# HashUnit4.net
KiCad netlist of a schematic drawn in Altium Designer
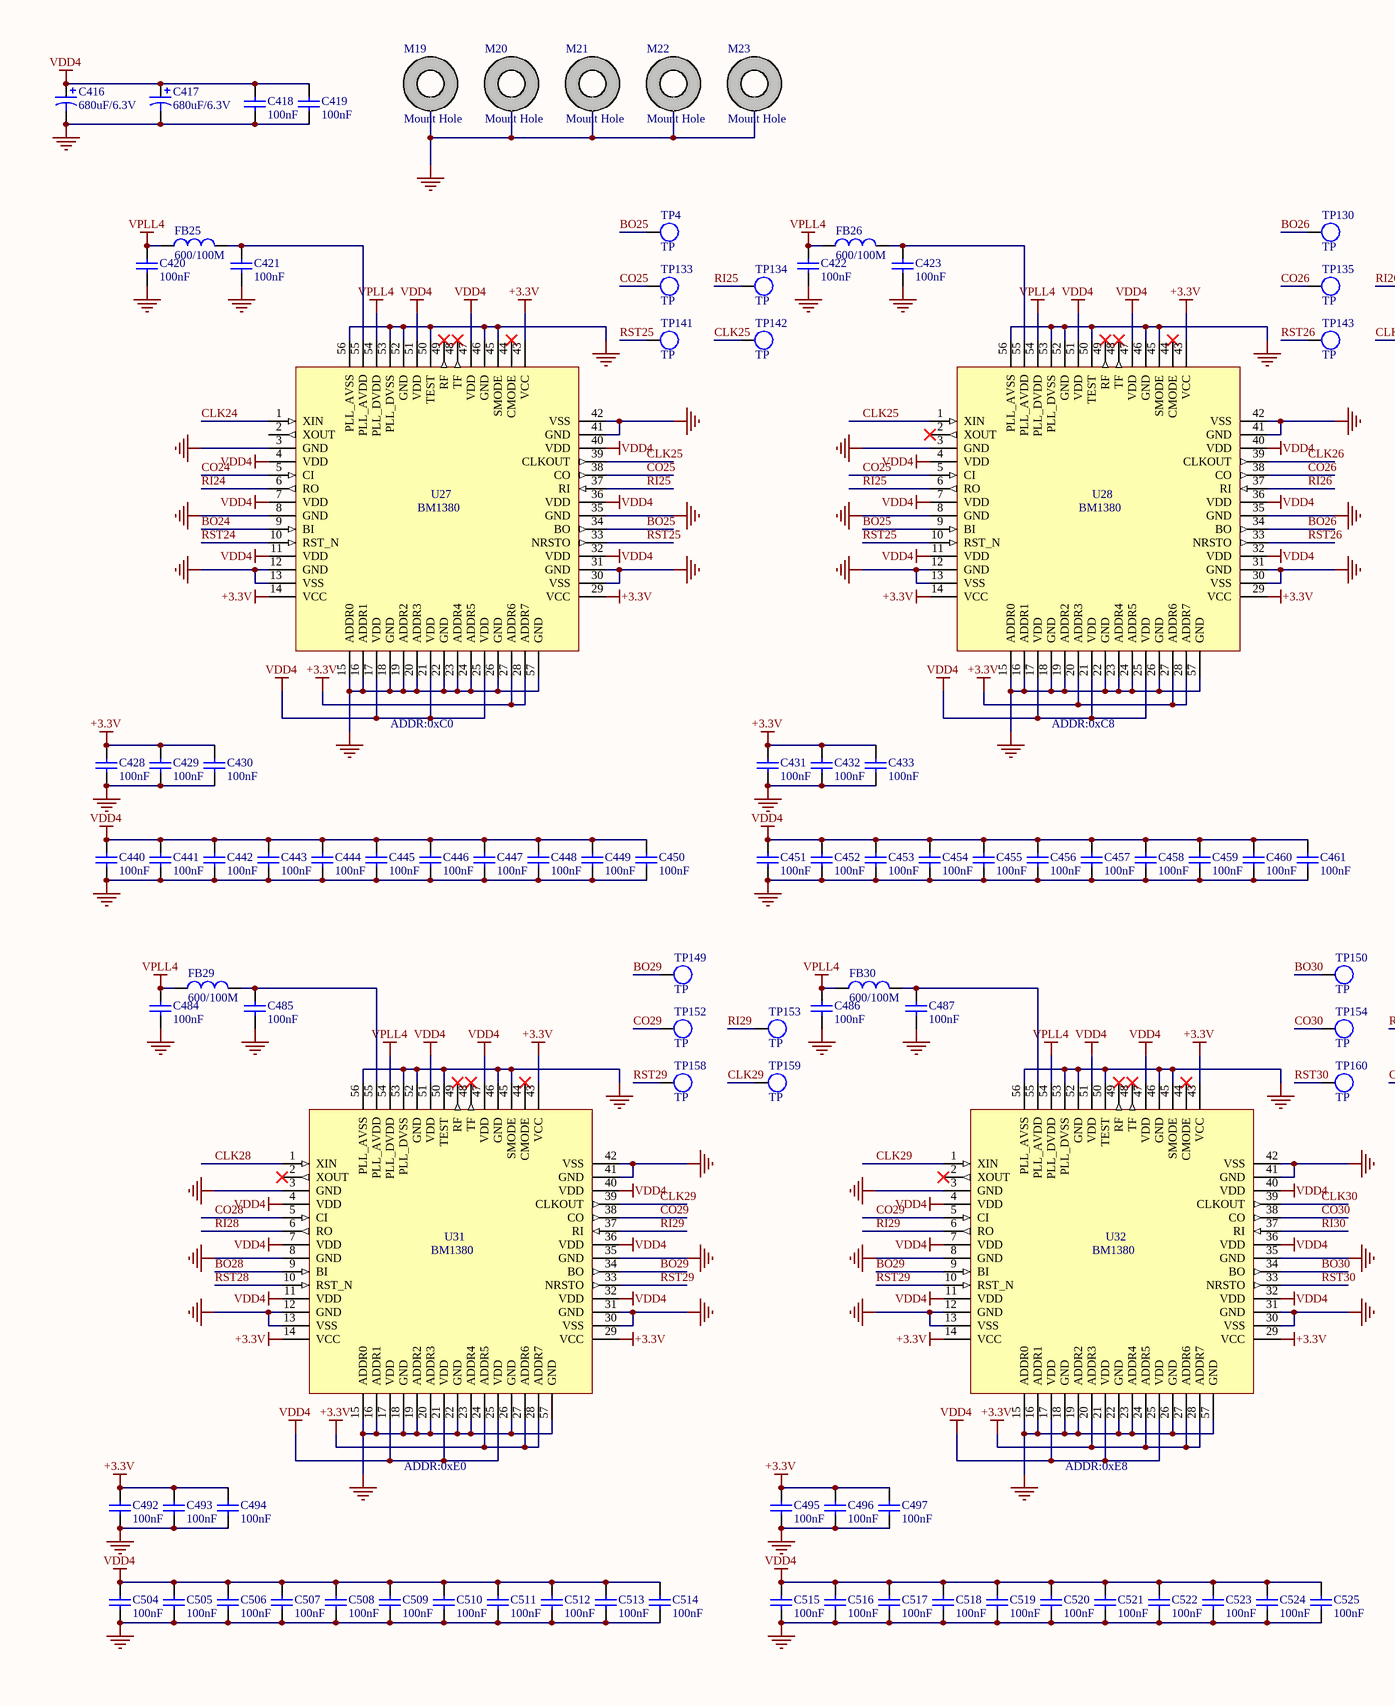
[diagram p0: HashUnit4.SchDoc, left]
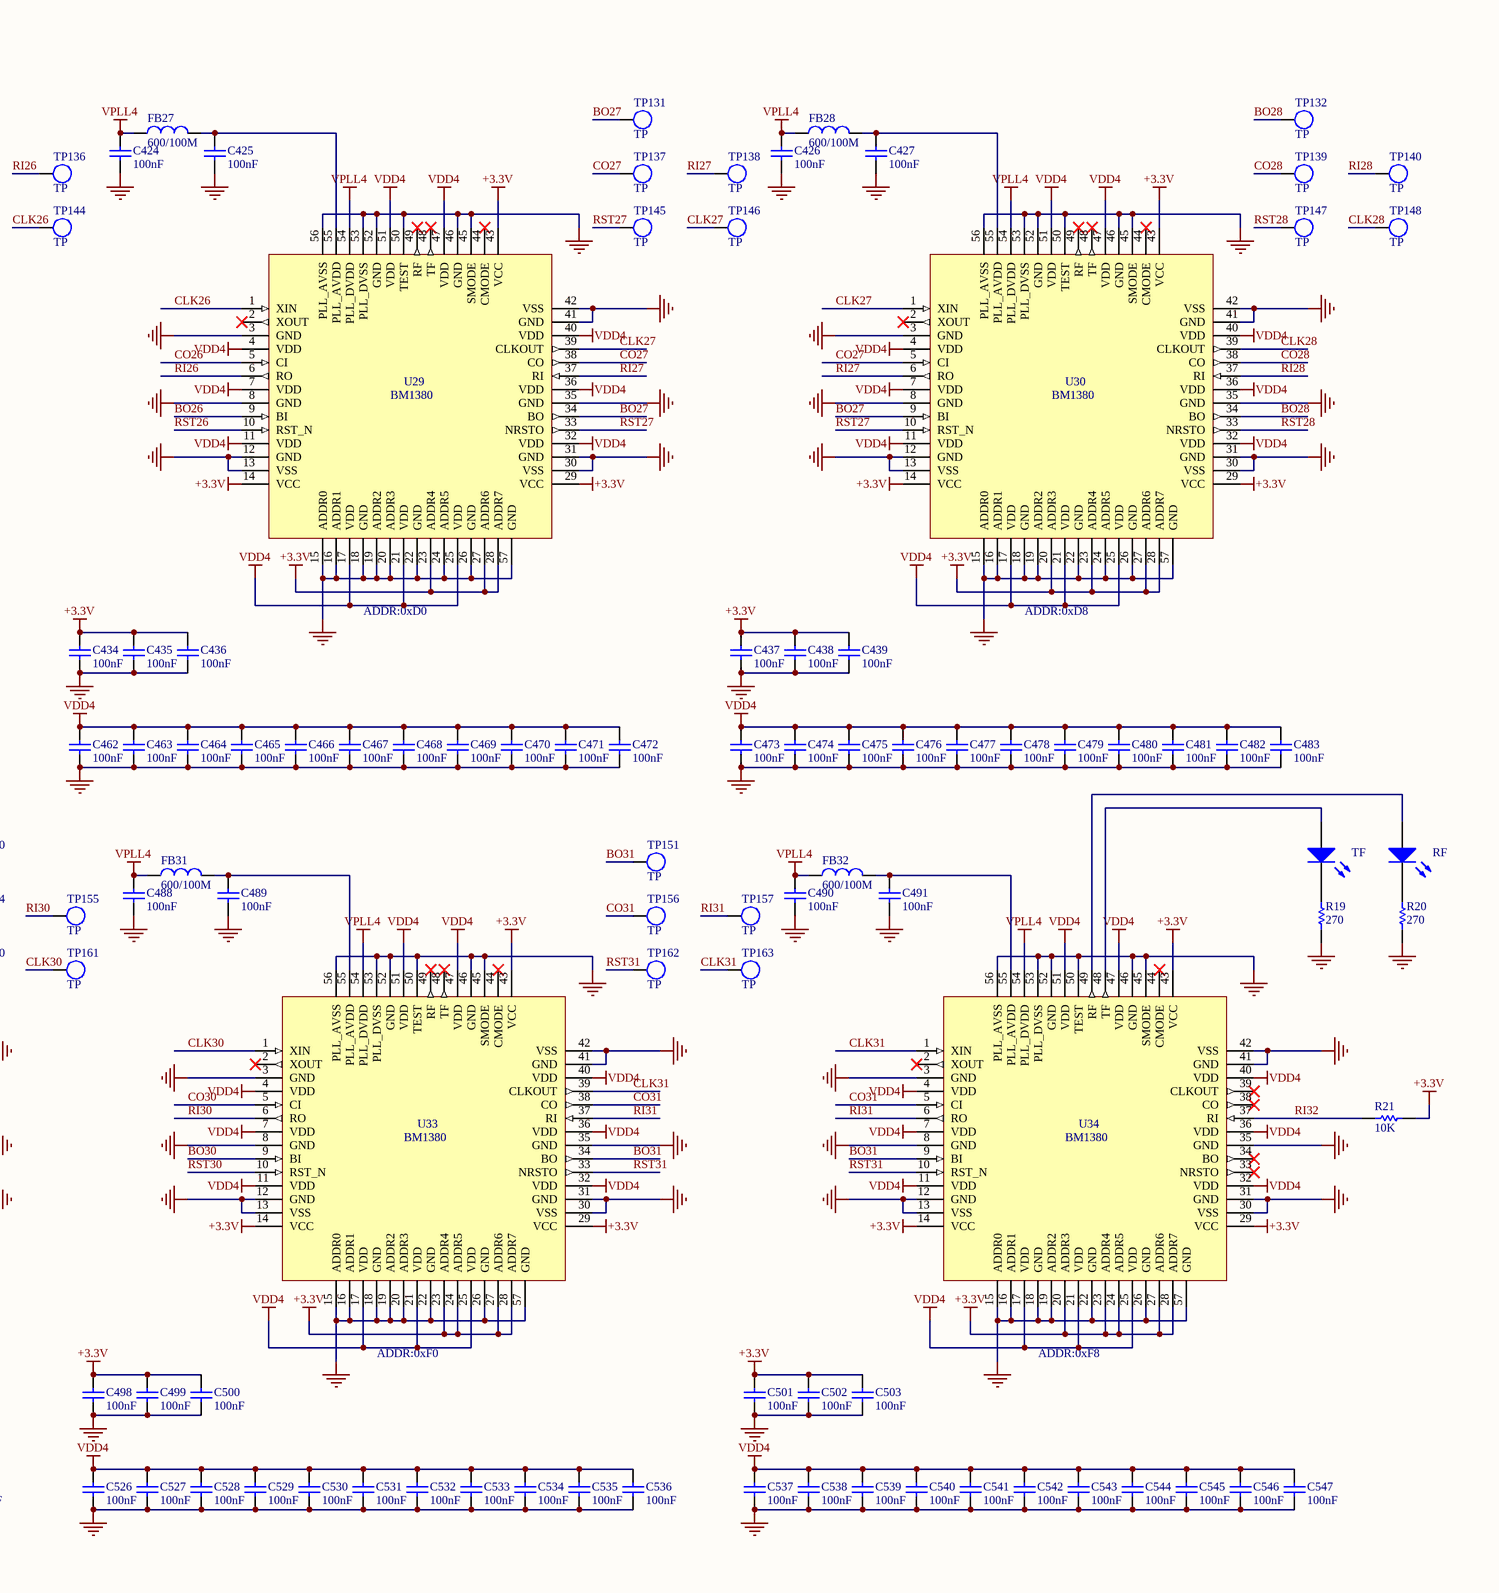
[diagram p1: HashUnit4.SchDoc, right]

(export (version "E")
  (design (tool "Eeschema 10.0.6"))
  (components
    (comp (ref "C416")
      (value "680uF/6.3V")
      (footprint "D")
      (description "Solid Tantalum Chip Capacitor, T492 Series - CWR11 Style Per Mil-PRF-55365/8")
      (fields (field (name "PUBLISHER") "Altium Limited"))
      (libsource (lib "KEMET Chip Capacitor") (part "T492C"))
    )
    (comp (ref "C417")
      (value "680uF/6.3V")
      (footprint "D")
      (description "Solid Tantalum Chip Capacitor, T492 Series - CWR11 Style Per Mil-PRF-55365/8")
      (fields (field (name "PUBLISHER") "Altium Limited"))
      (libsource (lib "KEMET Chip Capacitor") (part "T492C"))
    )
    (comp (ref "C418")
      (value "100nF")
      (footprint "CC0603(1608)")
      (description "Capacitor (Semiconductor SIM Model)")
      (fields (field (name "PUBLISHER") "Altium Limited"))
      (libsource (lib "Miscellaneous Devices") (part "Cap Semi"))
    )
    (comp (ref "C419")
      (value "100nF")
      (footprint "CC0603(1608)")
      (description "Capacitor (Semiconductor SIM Model)")
      (fields (field (name "PUBLISHER") "Altium Limited"))
      (libsource (lib "Miscellaneous Devices") (part "Cap Semi"))
    )
    (comp (ref "C420")
      (value "100nF")
      (footprint "CC0603(1608)")
      (description "Capacitor")
      (fields (field (name "PUBLISHER") "Altium Limited"))
      (libsource (lib "BitMain_Miner_1") (part "Cap"))
    )
    (comp (ref "C421")
      (value "100nF")
      (footprint "CC0603(1608)")
      (description "Capacitor")
      (fields (field (name "PUBLISHER") "Altium Limited"))
      (libsource (lib "BitMain_Miner_1") (part "Cap"))
    )
    (comp (ref "C422")
      (value "100nF")
      (footprint "CC0603(1608)")
      (description "Capacitor")
      (fields (field (name "PUBLISHER") "Altium Limited"))
      (libsource (lib "BitMain_Miner_1") (part "Cap"))
    )
    (comp (ref "C423")
      (value "100nF")
      (footprint "CC0603(1608)")
      (description "Capacitor")
      (fields (field (name "PUBLISHER") "Altium Limited"))
      (libsource (lib "BitMain_Miner_1") (part "Cap"))
    )
    (comp (ref "C424")
      (value "100nF")
      (footprint "CC0603(1608)")
      (description "Capacitor")
      (fields (field (name "PUBLISHER") "Altium Limited"))
      (libsource (lib "BitMain_Miner_1") (part "Cap"))
    )
    (comp (ref "C425")
      (value "100nF")
      (footprint "CC0603(1608)")
      (description "Capacitor")
      (fields (field (name "PUBLISHER") "Altium Limited"))
      (libsource (lib "BitMain_Miner_1") (part "Cap"))
    )
    (comp (ref "C426")
      (value "100nF")
      (footprint "CC0603(1608)")
      (description "Capacitor")
      (fields (field (name "PUBLISHER") "Altium Limited"))
      (libsource (lib "BitMain_Miner_1") (part "Cap"))
    )
    (comp (ref "C427")
      (value "100nF")
      (footprint "CC0603(1608)")
      (description "Capacitor")
      (fields (field (name "PUBLISHER") "Altium Limited"))
      (libsource (lib "BitMain_Miner_1") (part "Cap"))
    )
    (comp (ref "C428")
      (value "100nF")
      (footprint "CC0603(1608)")
      (description "Capacitor")
      (fields (field (name "PUBLISHER") "Altium Limited"))
      (libsource (lib "BitMain_Miner_1") (part "Cap"))
    )
    (comp (ref "C429")
      (value "100nF")
      (footprint "CC0603(1608)")
      (description "Capacitor")
      (fields (field (name "PUBLISHER") "Altium Limited"))
      (libsource (lib "BitMain_Miner_1") (part "Cap"))
    )
    (comp (ref "C430")
      (value "100nF")
      (footprint "CC0603(1608)")
      (description "Capacitor")
      (fields (field (name "PUBLISHER") "Altium Limited"))
      (libsource (lib "BitMain_Miner_1") (part "Cap"))
    )
    (comp (ref "C431")
      (value "100nF")
      (footprint "CC0603(1608)")
      (description "Capacitor")
      (fields (field (name "PUBLISHER") "Altium Limited"))
      (libsource (lib "BitMain_Miner_1") (part "Cap"))
    )
    (comp (ref "C432")
      (value "100nF")
      (footprint "CC0603(1608)")
      (description "Capacitor")
      (fields (field (name "PUBLISHER") "Altium Limited"))
      (libsource (lib "BitMain_Miner_1") (part "Cap"))
    )
    (comp (ref "C433")
      (value "100nF")
      (footprint "CC0603(1608)")
      (description "Capacitor")
      (fields (field (name "PUBLISHER") "Altium Limited"))
      (libsource (lib "BitMain_Miner_1") (part "Cap"))
    )
    (comp (ref "C434")
      (value "100nF")
      (footprint "CC0603(1608)")
      (description "Capacitor")
      (fields (field (name "PUBLISHER") "Altium Limited"))
      (libsource (lib "BitMain_Miner_1") (part "Cap"))
    )
    (comp (ref "C435")
      (value "100nF")
      (footprint "CC0603(1608)")
      (description "Capacitor")
      (fields (field (name "PUBLISHER") "Altium Limited"))
      (libsource (lib "BitMain_Miner_1") (part "Cap"))
    )
    (comp (ref "C436")
      (value "100nF")
      (footprint "CC0603(1608)")
      (description "Capacitor")
      (fields (field (name "PUBLISHER") "Altium Limited"))
      (libsource (lib "BitMain_Miner_1") (part "Cap"))
    )
    (comp (ref "C437")
      (value "100nF")
      (footprint "CC0603(1608)")
      (description "Capacitor")
      (fields (field (name "PUBLISHER") "Altium Limited"))
      (libsource (lib "BitMain_Miner_1") (part "Cap"))
    )
    (comp (ref "C438")
      (value "100nF")
      (footprint "CC0603(1608)")
      (description "Capacitor")
      (fields (field (name "PUBLISHER") "Altium Limited"))
      (libsource (lib "BitMain_Miner_1") (part "Cap"))
    )
    (comp (ref "C439")
      (value "100nF")
      (footprint "CC0603(1608)")
      (description "Capacitor")
      (fields (field (name "PUBLISHER") "Altium Limited"))
      (libsource (lib "BitMain_Miner_1") (part "Cap"))
    )
    (comp (ref "C440")
      (value "100nF")
      (footprint "CC0603(1608)")
      (description "Capacitor")
      (fields (field (name "PUBLISHER") "Altium Limited"))
      (libsource (lib "BitMain_Miner_1") (part "Cap"))
    )
    (comp (ref "C441")
      (value "100nF")
      (footprint "CC0603(1608)")
      (description "Capacitor")
      (fields (field (name "PUBLISHER") "Altium Limited"))
      (libsource (lib "BitMain_Miner_1") (part "Cap"))
    )
    (comp (ref "C442")
      (value "100nF")
      (footprint "CC0603(1608)")
      (description "Capacitor")
      (fields (field (name "PUBLISHER") "Altium Limited"))
      (libsource (lib "BitMain_Miner_1") (part "Cap"))
    )
    (comp (ref "C443")
      (value "100nF")
      (footprint "CC0603(1608)")
      (description "Capacitor")
      (fields (field (name "PUBLISHER") "Altium Limited"))
      (libsource (lib "BitMain_Miner_1") (part "Cap"))
    )
    (comp (ref "C444")
      (value "100nF")
      (footprint "CC0603(1608)")
      (description "Capacitor")
      (fields (field (name "PUBLISHER") "Altium Limited"))
      (libsource (lib "BitMain_Miner_1") (part "Cap"))
    )
    (comp (ref "C445")
      (value "100nF")
      (footprint "CC0603(1608)")
      (description "Capacitor")
      (fields (field (name "PUBLISHER") "Altium Limited"))
      (libsource (lib "BitMain_Miner_1") (part "Cap"))
    )
    (comp (ref "C446")
      (value "100nF")
      (footprint "CC0603(1608)")
      (description "Capacitor")
      (fields (field (name "PUBLISHER") "Altium Limited"))
      (libsource (lib "BitMain_Miner_1") (part "Cap"))
    )
    (comp (ref "C447")
      (value "100nF")
      (footprint "CC0603(1608)")
      (description "Capacitor")
      (fields (field (name "PUBLISHER") "Altium Limited"))
      (libsource (lib "BitMain_Miner_1") (part "Cap"))
    )
    (comp (ref "C448")
      (value "100nF")
      (footprint "CC0603(1608)")
      (description "Capacitor")
      (fields (field (name "PUBLISHER") "Altium Limited"))
      (libsource (lib "BitMain_Miner_1") (part "Cap"))
    )
    (comp (ref "C449")
      (value "100nF")
      (footprint "CC0603(1608)")
      (description "Capacitor")
      (fields (field (name "PUBLISHER") "Altium Limited"))
      (libsource (lib "BitMain_Miner_1") (part "Cap"))
    )
    (comp (ref "C450")
      (value "100nF")
      (footprint "CC0603(1608)")
      (description "Capacitor")
      (fields (field (name "PUBLISHER") "Altium Limited"))
      (libsource (lib "BitMain_Miner_1") (part "Cap"))
    )
    (comp (ref "C451")
      (value "100nF")
      (footprint "CC0603(1608)")
      (description "Capacitor")
      (fields (field (name "PUBLISHER") "Altium Limited"))
      (libsource (lib "BitMain_Miner_1") (part "Cap"))
    )
    (comp (ref "C452")
      (value "100nF")
      (footprint "CC0603(1608)")
      (description "Capacitor")
      (fields (field (name "PUBLISHER") "Altium Limited"))
      (libsource (lib "BitMain_Miner_1") (part "Cap"))
    )
    (comp (ref "C453")
      (value "100nF")
      (footprint "CC0603(1608)")
      (description "Capacitor")
      (fields (field (name "PUBLISHER") "Altium Limited"))
      (libsource (lib "BitMain_Miner_1") (part "Cap"))
    )
    (comp (ref "C454")
      (value "100nF")
      (footprint "CC0603(1608)")
      (description "Capacitor")
      (fields (field (name "PUBLISHER") "Altium Limited"))
      (libsource (lib "BitMain_Miner_1") (part "Cap"))
    )
    (comp (ref "C455")
      (value "100nF")
      (footprint "CC0603(1608)")
      (description "Capacitor")
      (fields (field (name "PUBLISHER") "Altium Limited"))
      (libsource (lib "BitMain_Miner_1") (part "Cap"))
    )
    (comp (ref "C456")
      (value "100nF")
      (footprint "CC0603(1608)")
      (description "Capacitor")
      (fields (field (name "PUBLISHER") "Altium Limited"))
      (libsource (lib "BitMain_Miner_1") (part "Cap"))
    )
    (comp (ref "C457")
      (value "100nF")
      (footprint "CC0603(1608)")
      (description "Capacitor")
      (fields (field (name "PUBLISHER") "Altium Limited"))
      (libsource (lib "BitMain_Miner_1") (part "Cap"))
    )
    (comp (ref "C458")
      (value "100nF")
      (footprint "CC0603(1608)")
      (description "Capacitor")
      (fields (field (name "PUBLISHER") "Altium Limited"))
      (libsource (lib "BitMain_Miner_1") (part "Cap"))
    )
    (comp (ref "C459")
      (value "100nF")
      (footprint "CC0603(1608)")
      (description "Capacitor")
      (fields (field (name "PUBLISHER") "Altium Limited"))
      (libsource (lib "BitMain_Miner_1") (part "Cap"))
    )
    (comp (ref "C460")
      (value "100nF")
      (footprint "CC0603(1608)")
      (description "Capacitor")
      (fields (field (name "PUBLISHER") "Altium Limited"))
      (libsource (lib "BitMain_Miner_1") (part "Cap"))
    )
    (comp (ref "C461")
      (value "100nF")
      (footprint "CC0603(1608)")
      (description "Capacitor")
      (fields (field (name "PUBLISHER") "Altium Limited"))
      (libsource (lib "BitMain_Miner_1") (part "Cap"))
    )
    (comp (ref "C462")
      (value "100nF")
      (footprint "CC0603(1608)")
      (description "Capacitor")
      (fields (field (name "PUBLISHER") "Altium Limited"))
      (libsource (lib "BitMain_Miner_1") (part "Cap"))
    )
    (comp (ref "C463")
      (value "100nF")
      (footprint "CC0603(1608)")
      (description "Capacitor")
      (fields (field (name "PUBLISHER") "Altium Limited"))
      (libsource (lib "BitMain_Miner_1") (part "Cap"))
    )
    (comp (ref "C464")
      (value "100nF")
      (footprint "CC0603(1608)")
      (description "Capacitor")
      (fields (field (name "PUBLISHER") "Altium Limited"))
      (libsource (lib "BitMain_Miner_1") (part "Cap"))
    )
    (comp (ref "C465")
      (value "100nF")
      (footprint "CC0603(1608)")
      (description "Capacitor")
      (fields (field (name "PUBLISHER") "Altium Limited"))
      (libsource (lib "BitMain_Miner_1") (part "Cap"))
    )
    (comp (ref "C466")
      (value "100nF")
      (footprint "CC0603(1608)")
      (description "Capacitor")
      (fields (field (name "PUBLISHER") "Altium Limited"))
      (libsource (lib "BitMain_Miner_1") (part "Cap"))
    )
    (comp (ref "C467")
      (value "100nF")
      (footprint "CC0603(1608)")
      (description "Capacitor")
      (fields (field (name "PUBLISHER") "Altium Limited"))
      (libsource (lib "BitMain_Miner_1") (part "Cap"))
    )
    (comp (ref "C468")
      (value "100nF")
      (footprint "CC0603(1608)")
      (description "Capacitor")
      (fields (field (name "PUBLISHER") "Altium Limited"))
      (libsource (lib "BitMain_Miner_1") (part "Cap"))
    )
    (comp (ref "C469")
      (value "100nF")
      (footprint "CC0603(1608)")
      (description "Capacitor")
      (fields (field (name "PUBLISHER") "Altium Limited"))
      (libsource (lib "BitMain_Miner_1") (part "Cap"))
    )
    (comp (ref "C470")
      (value "100nF")
      (footprint "CC0603(1608)")
      (description "Capacitor")
      (fields (field (name "PUBLISHER") "Altium Limited"))
      (libsource (lib "BitMain_Miner_1") (part "Cap"))
    )
    (comp (ref "C471")
      (value "100nF")
      (footprint "CC0603(1608)")
      (description "Capacitor")
      (fields (field (name "PUBLISHER") "Altium Limited"))
      (libsource (lib "BitMain_Miner_1") (part "Cap"))
    )
    (comp (ref "C472")
      (value "100nF")
      (footprint "CC0603(1608)")
      (description "Capacitor")
      (fields (field (name "PUBLISHER") "Altium Limited"))
      (libsource (lib "BitMain_Miner_1") (part "Cap"))
    )
    (comp (ref "C473")
      (value "100nF")
      (footprint "CC0603(1608)")
      (description "Capacitor")
      (fields (field (name "PUBLISHER") "Altium Limited"))
      (libsource (lib "BitMain_Miner_1") (part "Cap"))
    )
    (comp (ref "C474")
      (value "100nF")
      (footprint "CC0603(1608)")
      (description "Capacitor")
      (fields (field (name "PUBLISHER") "Altium Limited"))
      (libsource (lib "BitMain_Miner_1") (part "Cap"))
    )
    (comp (ref "C475")
      (value "100nF")
      (footprint "CC0603(1608)")
      (description "Capacitor")
      (fields (field (name "PUBLISHER") "Altium Limited"))
      (libsource (lib "BitMain_Miner_1") (part "Cap"))
    )
    (comp (ref "C476")
      (value "100nF")
      (footprint "CC0603(1608)")
      (description "Capacitor")
      (fields (field (name "PUBLISHER") "Altium Limited"))
      (libsource (lib "BitMain_Miner_1") (part "Cap"))
    )
    (comp (ref "C477")
      (value "100nF")
      (footprint "CC0603(1608)")
      (description "Capacitor")
      (fields (field (name "PUBLISHER") "Altium Limited"))
      (libsource (lib "BitMain_Miner_1") (part "Cap"))
    )
    (comp (ref "C478")
      (value "100nF")
      (footprint "CC0603(1608)")
      (description "Capacitor")
      (fields (field (name "PUBLISHER") "Altium Limited"))
      (libsource (lib "BitMain_Miner_1") (part "Cap"))
    )
    (comp (ref "C479")
      (value "100nF")
      (footprint "CC0603(1608)")
      (description "Capacitor")
      (fields (field (name "PUBLISHER") "Altium Limited"))
      (libsource (lib "BitMain_Miner_1") (part "Cap"))
    )
    (comp (ref "C480")
      (value "100nF")
      (footprint "CC0603(1608)")
      (description "Capacitor")
      (fields (field (name "PUBLISHER") "Altium Limited"))
      (libsource (lib "BitMain_Miner_1") (part "Cap"))
    )
    (comp (ref "C481")
      (value "100nF")
      (footprint "CC0603(1608)")
      (description "Capacitor")
      (fields (field (name "PUBLISHER") "Altium Limited"))
      (libsource (lib "BitMain_Miner_1") (part "Cap"))
    )
    (comp (ref "C482")
      (value "100nF")
      (footprint "CC0603(1608)")
      (description "Capacitor")
      (fields (field (name "PUBLISHER") "Altium Limited"))
      (libsource (lib "BitMain_Miner_1") (part "Cap"))
    )
    (comp (ref "C483")
      (value "100nF")
      (footprint "CC0603(1608)")
      (description "Capacitor")
      (fields (field (name "PUBLISHER") "Altium Limited"))
      (libsource (lib "BitMain_Miner_1") (part "Cap"))
    )
    (comp (ref "C484")
      (value "100nF")
      (footprint "CC0603(1608)")
      (description "Capacitor")
      (fields (field (name "PUBLISHER") "Altium Limited"))
      (libsource (lib "BitMain_Miner_1") (part "Cap"))
    )
    (comp (ref "C485")
      (value "100nF")
      (footprint "CC0603(1608)")
      (description "Capacitor")
      (fields (field (name "PUBLISHER") "Altium Limited"))
      (libsource (lib "BitMain_Miner_1") (part "Cap"))
    )
    (comp (ref "C486")
      (value "100nF")
      (footprint "CC0603(1608)")
      (description "Capacitor")
      (fields (field (name "PUBLISHER") "Altium Limited"))
      (libsource (lib "BitMain_Miner_1") (part "Cap"))
    )
    (comp (ref "C487")
      (value "100nF")
      (footprint "CC0603(1608)")
      (description "Capacitor")
      (fields (field (name "PUBLISHER") "Altium Limited"))
      (libsource (lib "BitMain_Miner_1") (part "Cap"))
    )
    (comp (ref "C488")
      (value "100nF")
      (footprint "CC0603(1608)")
      (description "Capacitor")
      (fields (field (name "PUBLISHER") "Altium Limited"))
      (libsource (lib "BitMain_Miner_1") (part "Cap"))
    )
    (comp (ref "C489")
      (value "100nF")
      (footprint "CC0603(1608)")
      (description "Capacitor")
      (fields (field (name "PUBLISHER") "Altium Limited"))
      (libsource (lib "BitMain_Miner_1") (part "Cap"))
    )
    (comp (ref "C490")
      (value "100nF")
      (footprint "CC0603(1608)")
      (description "Capacitor")
      (fields (field (name "PUBLISHER") "Altium Limited"))
      (libsource (lib "BitMain_Miner_1") (part "Cap"))
    )
    (comp (ref "C491")
      (value "100nF")
      (footprint "CC0603(1608)")
      (description "Capacitor")
      (fields (field (name "PUBLISHER") "Altium Limited"))
      (libsource (lib "BitMain_Miner_1") (part "Cap"))
    )
    (comp (ref "C492")
      (value "100nF")
      (footprint "CC0603(1608)")
      (description "Capacitor")
      (fields (field (name "PUBLISHER") "Altium Limited"))
      (libsource (lib "BitMain_Miner_1") (part "Cap"))
    )
    (comp (ref "C493")
      (value "100nF")
      (footprint "CC0603(1608)")
      (description "Capacitor")
      (fields (field (name "PUBLISHER") "Altium Limited"))
      (libsource (lib "BitMain_Miner_1") (part "Cap"))
    )
    (comp (ref "C494")
      (value "100nF")
      (footprint "CC0603(1608)")
      (description "Capacitor")
      (fields (field (name "PUBLISHER") "Altium Limited"))
      (libsource (lib "BitMain_Miner_1") (part "Cap"))
    )
    (comp (ref "C495")
      (value "100nF")
      (footprint "CC0603(1608)")
      (description "Capacitor")
      (fields (field (name "PUBLISHER") "Altium Limited"))
      (libsource (lib "BitMain_Miner_1") (part "Cap"))
    )
    (comp (ref "C496")
      (value "100nF")
      (footprint "CC0603(1608)")
      (description "Capacitor")
      (fields (field (name "PUBLISHER") "Altium Limited"))
      (libsource (lib "BitMain_Miner_1") (part "Cap"))
    )
    (comp (ref "C497")
      (value "100nF")
      (footprint "CC0603(1608)")
      (description "Capacitor")
      (fields (field (name "PUBLISHER") "Altium Limited"))
      (libsource (lib "BitMain_Miner_1") (part "Cap"))
    )
    (comp (ref "C498")
      (value "100nF")
      (footprint "CC0603(1608)")
      (description "Capacitor")
      (fields (field (name "PUBLISHER") "Altium Limited"))
      (libsource (lib "BitMain_Miner_1") (part "Cap"))
    )
    (comp (ref "C499")
      (value "100nF")
      (footprint "CC0603(1608)")
      (description "Capacitor")
      (fields (field (name "PUBLISHER") "Altium Limited"))
      (libsource (lib "BitMain_Miner_1") (part "Cap"))
    )
    (comp (ref "C500")
      (value "100nF")
      (footprint "CC0603(1608)")
      (description "Capacitor")
      (fields (field (name "PUBLISHER") "Altium Limited"))
      (libsource (lib "BitMain_Miner_1") (part "Cap"))
    )
    (comp (ref "C501")
      (value "100nF")
      (footprint "CC0603(1608)")
      (description "Capacitor")
      (fields (field (name "PUBLISHER") "Altium Limited"))
      (libsource (lib "BitMain_Miner_1") (part "Cap"))
    )
    (comp (ref "C502")
      (value "100nF")
      (footprint "CC0603(1608)")
      (description "Capacitor")
      (fields (field (name "PUBLISHER") "Altium Limited"))
      (libsource (lib "BitMain_Miner_1") (part "Cap"))
    )
    (comp (ref "C503")
      (value "100nF")
      (footprint "CC0603(1608)")
      (description "Capacitor")
      (fields (field (name "PUBLISHER") "Altium Limited"))
      (libsource (lib "BitMain_Miner_1") (part "Cap"))
    )
    (comp (ref "C504")
      (value "100nF")
      (footprint "CC0603(1608)")
      (description "Capacitor")
      (fields (field (name "PUBLISHER") "Altium Limited"))
      (libsource (lib "BitMain_Miner_1") (part "Cap"))
    )
    (comp (ref "C505")
      (value "100nF")
      (footprint "CC0603(1608)")
      (description "Capacitor")
      (fields (field (name "PUBLISHER") "Altium Limited"))
      (libsource (lib "BitMain_Miner_1") (part "Cap"))
    )
    (comp (ref "C506")
      (value "100nF")
      (footprint "CC0603(1608)")
      (description "Capacitor")
      (fields (field (name "PUBLISHER") "Altium Limited"))
      (libsource (lib "BitMain_Miner_1") (part "Cap"))
    )
    (comp (ref "C507")
      (value "100nF")
      (footprint "CC0603(1608)")
      (description "Capacitor")
      (fields (field (name "PUBLISHER") "Altium Limited"))
      (libsource (lib "BitMain_Miner_1") (part "Cap"))
    )
    (comp (ref "C508")
      (value "100nF")
      (footprint "CC0603(1608)")
      (description "Capacitor")
      (fields (field (name "PUBLISHER") "Altium Limited"))
      (libsource (lib "BitMain_Miner_1") (part "Cap"))
    )
    (comp (ref "C509")
      (value "100nF")
      (footprint "CC0603(1608)")
      (description "Capacitor")
      (fields (field (name "PUBLISHER") "Altium Limited"))
      (libsource (lib "BitMain_Miner_1") (part "Cap"))
    )
    (comp (ref "C510")
      (value "100nF")
      (footprint "CC0603(1608)")
      (description "Capacitor")
      (fields (field (name "PUBLISHER") "Altium Limited"))
      (libsource (lib "BitMain_Miner_1") (part "Cap"))
    )
    (comp (ref "C511")
      (value "100nF")
      (footprint "CC0603(1608)")
      (description "Capacitor")
      (fields (field (name "PUBLISHER") "Altium Limited"))
      (libsource (lib "BitMain_Miner_1") (part "Cap"))
    )
    (comp (ref "C512")
      (value "100nF")
      (footprint "CC0603(1608)")
      (description "Capacitor")
      (fields (field (name "PUBLISHER") "Altium Limited"))
      (libsource (lib "BitMain_Miner_1") (part "Cap"))
    )
    (comp (ref "C513")
      (value "100nF")
      (footprint "CC0603(1608)")
      (description "Capacitor")
      (fields (field (name "PUBLISHER") "Altium Limited"))
      (libsource (lib "BitMain_Miner_1") (part "Cap"))
    )
    (comp (ref "C514")
      (value "100nF")
      (footprint "CC0603(1608)")
      (description "Capacitor")
      (fields (field (name "PUBLISHER") "Altium Limited"))
      (libsource (lib "BitMain_Miner_1") (part "Cap"))
    )
    (comp (ref "C515")
      (value "100nF")
      (footprint "CC0603(1608)")
      (description "Capacitor")
      (fields (field (name "PUBLISHER") "Altium Limited"))
      (libsource (lib "BitMain_Miner_1") (part "Cap"))
    )
    (comp (ref "C516")
      (value "100nF")
      (footprint "CC0603(1608)")
      (description "Capacitor")
      (fields (field (name "PUBLISHER") "Altium Limited"))
      (libsource (lib "BitMain_Miner_1") (part "Cap"))
    )
    (comp (ref "C517")
      (value "100nF")
      (footprint "CC0603(1608)")
      (description "Capacitor")
      (fields (field (name "PUBLISHER") "Altium Limited"))
      (libsource (lib "BitMain_Miner_1") (part "Cap"))
    )
    (comp (ref "C518")
      (value "100nF")
      (footprint "CC0603(1608)")
      (description "Capacitor")
      (fields (field (name "PUBLISHER") "Altium Limited"))
      (libsource (lib "BitMain_Miner_1") (part "Cap"))
    )
    (comp (ref "C519")
      (value "100nF")
      (footprint "CC0603(1608)")
      (description "Capacitor")
      (fields (field (name "PUBLISHER") "Altium Limited"))
      (libsource (lib "BitMain_Miner_1") (part "Cap"))
    )
    (comp (ref "C520")
      (value "100nF")
      (footprint "CC0603(1608)")
      (description "Capacitor")
      (fields (field (name "PUBLISHER") "Altium Limited"))
      (libsource (lib "BitMain_Miner_1") (part "Cap"))
    )
    (comp (ref "C521")
      (value "100nF")
      (footprint "CC0603(1608)")
      (description "Capacitor")
      (fields (field (name "PUBLISHER") "Altium Limited"))
      (libsource (lib "BitMain_Miner_1") (part "Cap"))
    )
    (comp (ref "C522")
      (value "100nF")
      (footprint "CC0603(1608)")
      (description "Capacitor")
      (fields (field (name "PUBLISHER") "Altium Limited"))
      (libsource (lib "BitMain_Miner_1") (part "Cap"))
    )
    (comp (ref "C523")
      (value "100nF")
      (footprint "CC0603(1608)")
      (description "Capacitor")
      (fields (field (name "PUBLISHER") "Altium Limited"))
      (libsource (lib "BitMain_Miner_1") (part "Cap"))
    )
    (comp (ref "C524")
      (value "100nF")
      (footprint "CC0603(1608)")
      (description "Capacitor")
      (fields (field (name "PUBLISHER") "Altium Limited"))
      (libsource (lib "BitMain_Miner_1") (part "Cap"))
    )
    (comp (ref "C525")
      (value "100nF")
      (footprint "CC0603(1608)")
      (description "Capacitor")
      (fields (field (name "PUBLISHER") "Altium Limited"))
      (libsource (lib "BitMain_Miner_1") (part "Cap"))
    )
    (comp (ref "C526")
      (value "100nF")
      (footprint "CC0603(1608)")
      (description "Capacitor")
      (fields (field (name "PUBLISHER") "Altium Limited"))
      (libsource (lib "BitMain_Miner_1") (part "Cap"))
    )
    (comp (ref "C527")
      (value "100nF")
      (footprint "CC0603(1608)")
      (description "Capacitor")
      (fields (field (name "PUBLISHER") "Altium Limited"))
      (libsource (lib "BitMain_Miner_1") (part "Cap"))
    )
    (comp (ref "C528")
      (value "100nF")
      (footprint "CC0603(1608)")
      (description "Capacitor")
      (fields (field (name "PUBLISHER") "Altium Limited"))
      (libsource (lib "BitMain_Miner_1") (part "Cap"))
    )
    (comp (ref "C529")
      (value "100nF")
      (footprint "CC0603(1608)")
      (description "Capacitor")
      (fields (field (name "PUBLISHER") "Altium Limited"))
      (libsource (lib "BitMain_Miner_1") (part "Cap"))
    )
    (comp (ref "C530")
      (value "100nF")
      (footprint "CC0603(1608)")
      (description "Capacitor")
      (fields (field (name "PUBLISHER") "Altium Limited"))
      (libsource (lib "BitMain_Miner_1") (part "Cap"))
    )
    (comp (ref "C531")
      (value "100nF")
      (footprint "CC0603(1608)")
      (description "Capacitor")
      (fields (field (name "PUBLISHER") "Altium Limited"))
      (libsource (lib "BitMain_Miner_1") (part "Cap"))
    )
    (comp (ref "C532")
      (value "100nF")
      (footprint "CC0603(1608)")
      (description "Capacitor")
      (fields (field (name "PUBLISHER") "Altium Limited"))
      (libsource (lib "BitMain_Miner_1") (part "Cap"))
    )
    (comp (ref "C533")
      (value "100nF")
      (footprint "CC0603(1608)")
      (description "Capacitor")
      (fields (field (name "PUBLISHER") "Altium Limited"))
      (libsource (lib "BitMain_Miner_1") (part "Cap"))
    )
    (comp (ref "C534")
      (value "100nF")
      (footprint "CC0603(1608)")
      (description "Capacitor")
      (fields (field (name "PUBLISHER") "Altium Limited"))
      (libsource (lib "BitMain_Miner_1") (part "Cap"))
    )
    (comp (ref "C535")
      (value "100nF")
      (footprint "CC0603(1608)")
      (description "Capacitor")
      (fields (field (name "PUBLISHER") "Altium Limited"))
      (libsource (lib "BitMain_Miner_1") (part "Cap"))
    )
    (comp (ref "C536")
      (value "100nF")
      (footprint "CC0603(1608)")
      (description "Capacitor")
      (fields (field (name "PUBLISHER") "Altium Limited"))
      (libsource (lib "BitMain_Miner_1") (part "Cap"))
    )
    (comp (ref "C537")
      (value "100nF")
      (footprint "CC0603(1608)")
      (description "Capacitor")
      (fields (field (name "PUBLISHER") "Altium Limited"))
      (libsource (lib "BitMain_Miner_1") (part "Cap"))
    )
    (comp (ref "C538")
      (value "100nF")
      (footprint "CC0603(1608)")
      (description "Capacitor")
      (fields (field (name "PUBLISHER") "Altium Limited"))
      (libsource (lib "BitMain_Miner_1") (part "Cap"))
    )
    (comp (ref "C539")
      (value "100nF")
      (footprint "CC0603(1608)")
      (description "Capacitor")
      (fields (field (name "PUBLISHER") "Altium Limited"))
      (libsource (lib "BitMain_Miner_1") (part "Cap"))
    )
    (comp (ref "C540")
      (value "100nF")
      (footprint "CC0603(1608)")
      (description "Capacitor")
      (fields (field (name "PUBLISHER") "Altium Limited"))
      (libsource (lib "BitMain_Miner_1") (part "Cap"))
    )
    (comp (ref "C541")
      (value "100nF")
      (footprint "CC0603(1608)")
      (description "Capacitor")
      (fields (field (name "PUBLISHER") "Altium Limited"))
      (libsource (lib "BitMain_Miner_1") (part "Cap"))
    )
    (comp (ref "C542")
      (value "100nF")
      (footprint "CC0603(1608)")
      (description "Capacitor")
      (fields (field (name "PUBLISHER") "Altium Limited"))
      (libsource (lib "BitMain_Miner_1") (part "Cap"))
    )
    (comp (ref "C543")
      (value "100nF")
      (footprint "CC0603(1608)")
      (description "Capacitor")
      (fields (field (name "PUBLISHER") "Altium Limited"))
      (libsource (lib "BitMain_Miner_1") (part "Cap"))
    )
    (comp (ref "C544")
      (value "100nF")
      (footprint "CC0603(1608)")
      (description "Capacitor")
      (fields (field (name "PUBLISHER") "Altium Limited"))
      (libsource (lib "BitMain_Miner_1") (part "Cap"))
    )
    (comp (ref "C545")
      (value "100nF")
      (footprint "CC0603(1608)")
      (description "Capacitor")
      (fields (field (name "PUBLISHER") "Altium Limited"))
      (libsource (lib "BitMain_Miner_1") (part "Cap"))
    )
    (comp (ref "C546")
      (value "100nF")
      (footprint "CC0603(1608)")
      (description "Capacitor")
      (fields (field (name "PUBLISHER") "Altium Limited"))
      (libsource (lib "BitMain_Miner_1") (part "Cap"))
    )
    (comp (ref "C547")
      (value "100nF")
      (footprint "CC0603(1608)")
      (description "Capacitor")
      (fields (field (name "PUBLISHER") "Altium Limited"))
      (libsource (lib "BitMain_Miner_1") (part "Cap"))
    )
    (comp (ref "FB25")
      (value "600/100M")
      (footprint "FB0603(1608)")
      (description "Inductor")
      (fields (field (name "PUBLISHER") "Altium Limited"))
      (libsource (lib "BitMain_Miner_1") (part "FB"))
    )
    (comp (ref "FB26")
      (value "600/100M")
      (footprint "FB0603(1608)")
      (description "Inductor")
      (fields (field (name "PUBLISHER") "Altium Limited"))
      (libsource (lib "BitMain_Miner_1") (part "FB"))
    )
    (comp (ref "FB27")
      (value "600/100M")
      (footprint "FB0603(1608)")
      (description "Inductor")
      (fields (field (name "PUBLISHER") "Altium Limited"))
      (libsource (lib "BitMain_Miner_1") (part "FB"))
    )
    (comp (ref "FB28")
      (value "600/100M")
      (footprint "FB0603(1608)")
      (description "Inductor")
      (fields (field (name "PUBLISHER") "Altium Limited"))
      (libsource (lib "BitMain_Miner_1") (part "FB"))
    )
    (comp (ref "FB29")
      (value "600/100M")
      (footprint "FB0603(1608)")
      (description "Inductor")
      (fields (field (name "PUBLISHER") "Altium Limited"))
      (libsource (lib "BitMain_Miner_1") (part "FB"))
    )
    (comp (ref "FB30")
      (value "600/100M")
      (footprint "FB0603(1608)")
      (description "Inductor")
      (fields (field (name "PUBLISHER") "Altium Limited"))
      (libsource (lib "BitMain_Miner_1") (part "FB"))
    )
    (comp (ref "FB31")
      (value "600/100M")
      (footprint "FB0603(1608)")
      (description "Inductor")
      (fields (field (name "PUBLISHER") "Altium Limited"))
      (libsource (lib "BitMain_Miner_1") (part "FB"))
    )
    (comp (ref "FB32")
      (value "600/100M")
      (footprint "FB0603(1608)")
      (description "Inductor")
      (fields (field (name "PUBLISHER") "Altium Limited"))
      (libsource (lib "BitMain_Miner_1") (part "FB"))
    )
    (comp (ref "M19") (value "Mount Hole") (footprint "MHOLE2") (libsource (lib "S6_2") (part "M_Hole")))
    (comp (ref "M20") (value "Mount Hole") (footprint "MHOLE2") (libsource (lib "S6_2") (part "M_Hole")))
    (comp (ref "M21") (value "Mount Hole") (footprint "MHOLE2") (libsource (lib "S6_2") (part "M_Hole")))
    (comp (ref "M22") (value "Mount Hole") (footprint "MHOLE2") (libsource (lib "S6_2") (part "M_Hole")))
    (comp (ref "M23") (value "Mount Hole") (footprint "MHOLE2") (libsource (lib "S6_2") (part "M_Hole")))
    (comp (ref "R19")
      (value "270")
      (footprint "RR0603(1608)")
      (description "Resistor")
      (libsource (lib "TPS53355_Test") (part "Res1"))
    )
    (comp (ref "R20")
      (value "270")
      (footprint "RR0603(1608)")
      (description "Resistor")
      (libsource (lib "TPS53355_Test") (part "Res1"))
    )
    (comp (ref "R21")
      (value "10K")
      (footprint "RR0603(1608)")
      (description "Resistor")
      (fields (field (name "PUBLISHER") "Altium Limited"))
      (libsource (lib "BitMain_Miner_1") (part "Res1"))
    )
    (comp (ref "RF")
      (value "Green")
      (footprint "LED0603(1608)")
      (description "Typical INFRARED GaAs LED")
      (fields (field (name "PUBLISHER") "Altium Limited"))
      (libsource (lib "Miscellaneous Devices") (part "LED0"))
    )
    (comp (ref "TF")
      (value "Green")
      (footprint "LED0603(1608)")
      (description "Typical INFRARED GaAs LED")
      (fields (field (name "PUBLISHER") "Altium Limited"))
      (libsource (lib "Miscellaneous Devices") (part "LED0"))
    )
    (comp (ref "TP4")
      (value "TP")
      (footprint "TP_SMD")
      (description "Test Point")
      (libsource (lib "BitMain_Miner_1") (part "TP"))
    )
    (comp (ref "TP130")
      (value "TP")
      (footprint "TP_SMD")
      (description "Test Point")
      (libsource (lib "BitMain_Miner_1") (part "TP"))
    )
    (comp (ref "TP131")
      (value "TP")
      (footprint "TP_SMD")
      (description "Test Point")
      (libsource (lib "BitMain_Miner_1") (part "TP"))
    )
    (comp (ref "TP132")
      (value "TP")
      (footprint "TP_SMD")
      (description "Test Point")
      (libsource (lib "BitMain_Miner_1") (part "TP"))
    )
    (comp (ref "TP133")
      (value "TP")
      (footprint "TP_SMD")
      (description "Test Point")
      (libsource (lib "BitMain_Miner_1") (part "TP"))
    )
    (comp (ref "TP134")
      (value "TP")
      (footprint "TP_SMD")
      (description "Test Point")
      (libsource (lib "BitMain_Miner_1") (part "TP"))
    )
    (comp (ref "TP135")
      (value "TP")
      (footprint "TP_SMD")
      (description "Test Point")
      (libsource (lib "BitMain_Miner_1") (part "TP"))
    )
    (comp (ref "TP136")
      (value "TP")
      (footprint "TP_SMD")
      (description "Test Point")
      (libsource (lib "BitMain_Miner_1") (part "TP"))
    )
    (comp (ref "TP137")
      (value "TP")
      (footprint "TP_SMD")
      (description "Test Point")
      (libsource (lib "BitMain_Miner_1") (part "TP"))
    )
    (comp (ref "TP138")
      (value "TP")
      (footprint "TP_SMD")
      (description "Test Point")
      (libsource (lib "BitMain_Miner_1") (part "TP"))
    )
    (comp (ref "TP139")
      (value "TP")
      (footprint "TP_SMD")
      (description "Test Point")
      (libsource (lib "BitMain_Miner_1") (part "TP"))
    )
    (comp (ref "TP140")
      (value "TP")
      (footprint "TP_SMD")
      (description "Test Point")
      (libsource (lib "BitMain_Miner_1") (part "TP"))
    )
    (comp (ref "TP141")
      (value "TP")
      (footprint "TP_SMD")
      (description "Test Point")
      (libsource (lib "BitMain_Miner_1") (part "TP"))
    )
    (comp (ref "TP142")
      (value "TP")
      (footprint "TP_SMD")
      (description "Test Point")
      (libsource (lib "BitMain_Miner_1") (part "TP"))
    )
    (comp (ref "TP143")
      (value "TP")
      (footprint "TP_SMD")
      (description "Test Point")
      (libsource (lib "BitMain_Miner_1") (part "TP"))
    )
    (comp (ref "TP144")
      (value "TP")
      (footprint "TP_SMD")
      (description "Test Point")
      (libsource (lib "BitMain_Miner_1") (part "TP"))
    )
    (comp (ref "TP145")
      (value "TP")
      (footprint "TP_SMD")
      (description "Test Point")
      (libsource (lib "BitMain_Miner_1") (part "TP"))
    )
    (comp (ref "TP146")
      (value "TP")
      (footprint "TP_SMD")
      (description "Test Point")
      (libsource (lib "BitMain_Miner_1") (part "TP"))
    )
    (comp (ref "TP147")
      (value "TP")
      (footprint "TP_SMD")
      (description "Test Point")
      (libsource (lib "BitMain_Miner_1") (part "TP"))
    )
    (comp (ref "TP148")
      (value "TP")
      (footprint "TP_SMD")
      (description "Test Point")
      (libsource (lib "BitMain_Miner_1") (part "TP"))
    )
    (comp (ref "TP149")
      (value "TP")
      (footprint "TP_SMD")
      (description "Test Point")
      (libsource (lib "BitMain_Miner_1") (part "TP"))
    )
    (comp (ref "TP150")
      (value "TP")
      (footprint "TP_SMD")
      (description "Test Point")
      (libsource (lib "BitMain_Miner_1") (part "TP"))
    )
    (comp (ref "TP151")
      (value "TP")
      (footprint "TP_SMD")
      (description "Test Point")
      (libsource (lib "BitMain_Miner_1") (part "TP"))
    )
    (comp (ref "TP152")
      (value "TP")
      (footprint "TP_SMD")
      (description "Test Point")
      (libsource (lib "BitMain_Miner_1") (part "TP"))
    )
    (comp (ref "TP153")
      (value "TP")
      (footprint "TP_SMD")
      (description "Test Point")
      (libsource (lib "BitMain_Miner_1") (part "TP"))
    )
    (comp (ref "TP154")
      (value "TP")
      (footprint "TP_SMD")
      (description "Test Point")
      (libsource (lib "BitMain_Miner_1") (part "TP"))
    )
    (comp (ref "TP155")
      (value "TP")
      (footprint "TP_SMD")
      (description "Test Point")
      (libsource (lib "BitMain_Miner_1") (part "TP"))
    )
    (comp (ref "TP156")
      (value "TP")
      (footprint "TP_SMD")
      (description "Test Point")
      (libsource (lib "BitMain_Miner_1") (part "TP"))
    )
    (comp (ref "TP157")
      (value "TP")
      (footprint "TP_SMD")
      (description "Test Point")
      (libsource (lib "BitMain_Miner_1") (part "TP"))
    )
    (comp (ref "TP158")
      (value "TP")
      (footprint "TP_SMD")
      (description "Test Point")
      (libsource (lib "BitMain_Miner_1") (part "TP"))
    )
    (comp (ref "TP159")
      (value "TP")
      (footprint "TP_SMD")
      (description "Test Point")
      (libsource (lib "BitMain_Miner_1") (part "TP"))
    )
    (comp (ref "TP160")
      (value "TP")
      (footprint "TP_SMD")
      (description "Test Point")
      (libsource (lib "BitMain_Miner_1") (part "TP"))
    )
    (comp (ref "TP161")
      (value "TP")
      (footprint "TP_SMD")
      (description "Test Point")
      (libsource (lib "BitMain_Miner_1") (part "TP"))
    )
    (comp (ref "TP162")
      (value "TP")
      (footprint "TP_SMD")
      (description "Test Point")
      (libsource (lib "BitMain_Miner_1") (part "TP"))
    )
    (comp (ref "TP163")
      (value "TP")
      (footprint "TP_SMD")
      (description "Test Point")
      (libsource (lib "BitMain_Miner_1") (part "TP"))
    )
    (comp (ref "U27") (value "BM1380") (footprint "QFN56") (libsource (lib "ANT_Miner_V1.3") (part "BM1380")))
    (comp (ref "U28") (value "BM1380") (footprint "QFN56") (libsource (lib "ANT_Miner_V1.3") (part "BM1380")))
    (comp (ref "U29") (value "BM1380") (footprint "QFN56") (libsource (lib "ANT_Miner_V1.3") (part "BM1380")))
    (comp (ref "U30") (value "BM1380") (footprint "QFN56") (libsource (lib "ANT_Miner_V1.3") (part "BM1380")))
    (comp (ref "U31") (value "BM1380") (footprint "QFN56") (libsource (lib "ANT_Miner_V1.3") (part "BM1380")))
    (comp (ref "U32") (value "BM1380") (footprint "QFN56") (libsource (lib "ANT_Miner_V1.3") (part "BM1380")))
    (comp (ref "U33") (value "BM1380") (footprint "QFN56") (libsource (lib "ANT_Miner_V1.3") (part "BM1380")))
    (comp (ref "U34") (value "BM1380") (footprint "QFN56") (libsource (lib "ANT_Miner_V1.3") (part "BM1380")))
  )
  (nets
    (net (code "1") (name "+3.3V") (class "Default")
      (node (ref "C428") (pin "2") (pinfunction "2_2") (pintype "passive"))
      (node (ref "C429") (pin "2") (pinfunction "2_2") (pintype "passive"))
      (node (ref "C430") (pin "2") (pinfunction "2_2") (pintype "passive"))
      (node (ref "C431") (pin "2") (pinfunction "2_2") (pintype "passive"))
      (node (ref "C432") (pin "2") (pinfunction "2_2") (pintype "passive"))
      (node (ref "C433") (pin "2") (pinfunction "2_2") (pintype "passive"))
      (node (ref "C434") (pin "2") (pinfunction "2_2") (pintype "passive"))
      (node (ref "C435") (pin "2") (pinfunction "2_2") (pintype "passive"))
      (node (ref "C436") (pin "2") (pinfunction "2_2") (pintype "passive"))
      (node (ref "C437") (pin "2") (pinfunction "2_2") (pintype "passive"))
      (node (ref "C438") (pin "2") (pinfunction "2_2") (pintype "passive"))
      (node (ref "C439") (pin "2") (pinfunction "2_2") (pintype "passive"))
      (node (ref "C492") (pin "2") (pinfunction "2_2") (pintype "passive"))
      (node (ref "C493") (pin "2") (pinfunction "2_2") (pintype "passive"))
      (node (ref "C494") (pin "2") (pinfunction "2_2") (pintype "passive"))
      (node (ref "C495") (pin "2") (pinfunction "2_2") (pintype "passive"))
      (node (ref "C496") (pin "2") (pinfunction "2_2") (pintype "passive"))
      (node (ref "C497") (pin "2") (pinfunction "2_2") (pintype "passive"))
      (node (ref "C498") (pin "2") (pinfunction "2_2") (pintype "passive"))
      (node (ref "C499") (pin "2") (pinfunction "2_2") (pintype "passive"))
      (node (ref "C500") (pin "2") (pinfunction "2_2") (pintype "passive"))
      (node (ref "C501") (pin "2") (pinfunction "2_2") (pintype "passive"))
      (node (ref "C502") (pin "2") (pinfunction "2_2") (pintype "passive"))
      (node (ref "C503") (pin "2") (pinfunction "2_2") (pintype "passive"))
      (node (ref "R21") (pin "2") (pinfunction "2_2") (pintype "passive"))
      (node (ref "U27") (pin "14") (pinfunction "VCC_14") (pintype "power_in"))
      (node (ref "U27") (pin "27") (pinfunction "ADDR6_27") (pintype "passive"))
      (node (ref "U27") (pin "28") (pinfunction "ADDR7_28") (pintype "passive"))
      (node (ref "U27") (pin "29") (pinfunction "VCC_29") (pintype "power_in"))
      (node (ref "U27") (pin "43") (pinfunction "VCC_43") (pintype "power_in"))
      (node (ref "U28") (pin "14") (pinfunction "VCC_14") (pintype "power_in"))
      (node (ref "U28") (pin "20") (pinfunction "ADDR3_20") (pintype "passive"))
      (node (ref "U28") (pin "27") (pinfunction "ADDR6_27") (pintype "passive"))
      (node (ref "U28") (pin "28") (pinfunction "ADDR7_28") (pintype "passive"))
      (node (ref "U28") (pin "29") (pinfunction "VCC_29") (pintype "power_in"))
      (node (ref "U28") (pin "43") (pinfunction "VCC_43") (pintype "power_in"))
      (node (ref "U29") (pin "14") (pinfunction "VCC_14") (pintype "power_in"))
      (node (ref "U29") (pin "23") (pinfunction "ADDR4_23") (pintype "passive"))
      (node (ref "U29") (pin "27") (pinfunction "ADDR6_27") (pintype "passive"))
      (node (ref "U29") (pin "28") (pinfunction "ADDR7_28") (pintype "passive"))
      (node (ref "U29") (pin "29") (pinfunction "VCC_29") (pintype "power_in"))
      (node (ref "U29") (pin "43") (pinfunction "VCC_43") (pintype "power_in"))
      (node (ref "U30") (pin "14") (pinfunction "VCC_14") (pintype "power_in"))
      (node (ref "U30") (pin "20") (pinfunction "ADDR3_20") (pintype "passive"))
      (node (ref "U30") (pin "23") (pinfunction "ADDR4_23") (pintype "passive"))
      (node (ref "U30") (pin "27") (pinfunction "ADDR6_27") (pintype "passive"))
      (node (ref "U30") (pin "28") (pinfunction "ADDR7_28") (pintype "passive"))
      (node (ref "U30") (pin "29") (pinfunction "VCC_29") (pintype "power_in"))
      (node (ref "U30") (pin "43") (pinfunction "VCC_43") (pintype "power_in"))
      (node (ref "U31") (pin "14") (pinfunction "VCC_14") (pintype "power_in"))
      (node (ref "U31") (pin "24") (pinfunction "ADDR5_24") (pintype "passive"))
      (node (ref "U31") (pin "27") (pinfunction "ADDR6_27") (pintype "passive"))
      (node (ref "U31") (pin "28") (pinfunction "ADDR7_28") (pintype "passive"))
      (node (ref "U31") (pin "29") (pinfunction "VCC_29") (pintype "power_in"))
      (node (ref "U31") (pin "43") (pinfunction "VCC_43") (pintype "power_in"))
      (node (ref "U32") (pin "14") (pinfunction "VCC_14") (pintype "power_in"))
      (node (ref "U32") (pin "20") (pinfunction "ADDR3_20") (pintype "passive"))
      (node (ref "U32") (pin "24") (pinfunction "ADDR5_24") (pintype "passive"))
      (node (ref "U32") (pin "27") (pinfunction "ADDR6_27") (pintype "passive"))
      (node (ref "U32") (pin "28") (pinfunction "ADDR7_28") (pintype "passive"))
      (node (ref "U32") (pin "29") (pinfunction "VCC_29") (pintype "power_in"))
      (node (ref "U32") (pin "43") (pinfunction "VCC_43") (pintype "power_in"))
      (node (ref "U33") (pin "14") (pinfunction "VCC_14") (pintype "power_in"))
      (node (ref "U33") (pin "23") (pinfunction "ADDR4_23") (pintype "passive"))
      (node (ref "U33") (pin "24") (pinfunction "ADDR5_24") (pintype "passive"))
      (node (ref "U33") (pin "27") (pinfunction "ADDR6_27") (pintype "passive"))
      (node (ref "U33") (pin "28") (pinfunction "ADDR7_28") (pintype "passive"))
      (node (ref "U33") (pin "29") (pinfunction "VCC_29") (pintype "power_in"))
      (node (ref "U33") (pin "43") (pinfunction "VCC_43") (pintype "power_in"))
      (node (ref "U34") (pin "14") (pinfunction "VCC_14") (pintype "power_in"))
      (node (ref "U34") (pin "20") (pinfunction "ADDR3_20") (pintype "passive"))
      (node (ref "U34") (pin "23") (pinfunction "ADDR4_23") (pintype "passive"))
      (node (ref "U34") (pin "24") (pinfunction "ADDR5_24") (pintype "passive"))
      (node (ref "U34") (pin "27") (pinfunction "ADDR6_27") (pintype "passive"))
      (node (ref "U34") (pin "28") (pinfunction "ADDR7_28") (pintype "passive"))
      (node (ref "U34") (pin "29") (pinfunction "VCC_29") (pintype "power_in"))
      (node (ref "U34") (pin "43") (pinfunction "VCC_43") (pintype "power_in"))
    )
    (net (code "2") (name "/BO24") (class "Default")
      (node (ref "U27") (pin "9") (pinfunction "BI_9") (pintype "input"))
    )
    (net (code "3") (name "/BO25") (class "Default")
      (node (ref "TP4") (pin "1") (pinfunction "1_1") (pintype "passive"))
      (node (ref "U27") (pin "34") (pinfunction "BO_34") (pintype "output"))
      (node (ref "U28") (pin "9") (pinfunction "BI_9") (pintype "input"))
    )
    (net (code "4") (name "/BO26") (class "Default")
      (node (ref "TP130") (pin "1") (pinfunction "1_1") (pintype "passive"))
      (node (ref "U28") (pin "34") (pinfunction "BO_34") (pintype "output"))
      (node (ref "U29") (pin "9") (pinfunction "BI_9") (pintype "input"))
    )
    (net (code "5") (name "/BO27") (class "Default")
      (node (ref "TP131") (pin "1") (pinfunction "1_1") (pintype "passive"))
      (node (ref "U29") (pin "34") (pinfunction "BO_34") (pintype "output"))
      (node (ref "U30") (pin "9") (pinfunction "BI_9") (pintype "input"))
    )
    (net (code "6") (name "/BO28") (class "Default")
      (node (ref "TP132") (pin "1") (pinfunction "1_1") (pintype "passive"))
      (node (ref "U30") (pin "34") (pinfunction "BO_34") (pintype "output"))
      (node (ref "U31") (pin "9") (pinfunction "BI_9") (pintype "input"))
    )
    (net (code "7") (name "/BO29") (class "Default")
      (node (ref "TP149") (pin "1") (pinfunction "1_1") (pintype "passive"))
      (node (ref "U31") (pin "34") (pinfunction "BO_34") (pintype "output"))
      (node (ref "U32") (pin "9") (pinfunction "BI_9") (pintype "input"))
    )
    (net (code "8") (name "/BO30") (class "Default")
      (node (ref "TP150") (pin "1") (pinfunction "1_1") (pintype "passive"))
      (node (ref "U32") (pin "34") (pinfunction "BO_34") (pintype "output"))
      (node (ref "U33") (pin "9") (pinfunction "BI_9") (pintype "input"))
    )
    (net (code "9") (name "/BO31") (class "Default")
      (node (ref "TP151") (pin "1") (pinfunction "1_1") (pintype "passive"))
      (node (ref "U33") (pin "34") (pinfunction "BO_34") (pintype "output"))
      (node (ref "U34") (pin "9") (pinfunction "BI_9") (pintype "input"))
    )
    (net (code "10") (name "/CLK24") (class "Default")
      (node (ref "U27") (pin "1") (pinfunction "XIN_1") (pintype "input"))
    )
    (net (code "11") (name "/CLK25") (class "Default")
      (node (ref "TP142") (pin "1") (pinfunction "1_1") (pintype "passive"))
      (node (ref "U27") (pin "39") (pinfunction "CLKOUT_39") (pintype "output"))
      (node (ref "U28") (pin "1") (pinfunction "XIN_1") (pintype "input"))
    )
    (net (code "12") (name "/CLK26") (class "Default")
      (node (ref "TP144") (pin "1") (pinfunction "1_1") (pintype "passive"))
      (node (ref "U28") (pin "39") (pinfunction "CLKOUT_39") (pintype "output"))
      (node (ref "U29") (pin "1") (pinfunction "XIN_1") (pintype "input"))
    )
    (net (code "13") (name "/CLK27") (class "Default")
      (node (ref "TP146") (pin "1") (pinfunction "1_1") (pintype "passive"))
      (node (ref "U29") (pin "39") (pinfunction "CLKOUT_39") (pintype "output"))
      (node (ref "U30") (pin "1") (pinfunction "XIN_1") (pintype "input"))
    )
    (net (code "14") (name "/CLK28") (class "Default")
      (node (ref "TP148") (pin "1") (pinfunction "1_1") (pintype "passive"))
      (node (ref "U30") (pin "39") (pinfunction "CLKOUT_39") (pintype "output"))
      (node (ref "U31") (pin "1") (pinfunction "XIN_1") (pintype "input"))
    )
    (net (code "15") (name "/CLK29") (class "Default")
      (node (ref "TP159") (pin "1") (pinfunction "1_1") (pintype "passive"))
      (node (ref "U31") (pin "39") (pinfunction "CLKOUT_39") (pintype "output"))
      (node (ref "U32") (pin "1") (pinfunction "XIN_1") (pintype "input"))
    )
    (net (code "16") (name "/CLK30") (class "Default")
      (node (ref "TP161") (pin "1") (pinfunction "1_1") (pintype "passive"))
      (node (ref "U32") (pin "39") (pinfunction "CLKOUT_39") (pintype "output"))
      (node (ref "U33") (pin "1") (pinfunction "XIN_1") (pintype "input"))
    )
    (net (code "17") (name "/CLK31") (class "Default")
      (node (ref "TP163") (pin "1") (pinfunction "1_1") (pintype "passive"))
      (node (ref "U33") (pin "39") (pinfunction "CLKOUT_39") (pintype "output"))
      (node (ref "U34") (pin "1") (pinfunction "XIN_1") (pintype "input"))
    )
    (net (code "18") (name "/CO24") (class "Default")
      (node (ref "U27") (pin "5") (pinfunction "CI_5") (pintype "input"))
    )
    (net (code "19") (name "/CO25") (class "Default")
      (node (ref "TP133") (pin "1") (pinfunction "1_1") (pintype "passive"))
      (node (ref "U27") (pin "38") (pinfunction "CO_38") (pintype "output"))
      (node (ref "U28") (pin "5") (pinfunction "CI_5") (pintype "input"))
    )
    (net (code "20") (name "/CO26") (class "Default")
      (node (ref "TP135") (pin "1") (pinfunction "1_1") (pintype "passive"))
      (node (ref "U28") (pin "38") (pinfunction "CO_38") (pintype "output"))
      (node (ref "U29") (pin "5") (pinfunction "CI_5") (pintype "input"))
    )
    (net (code "21") (name "/CO27") (class "Default")
      (node (ref "TP137") (pin "1") (pinfunction "1_1") (pintype "passive"))
      (node (ref "U29") (pin "38") (pinfunction "CO_38") (pintype "output"))
      (node (ref "U30") (pin "5") (pinfunction "CI_5") (pintype "input"))
    )
    (net (code "22") (name "/CO28") (class "Default")
      (node (ref "TP139") (pin "1") (pinfunction "1_1") (pintype "passive"))
      (node (ref "U30") (pin "38") (pinfunction "CO_38") (pintype "output"))
      (node (ref "U31") (pin "5") (pinfunction "CI_5") (pintype "input"))
    )
    (net (code "23") (name "/CO29") (class "Default")
      (node (ref "TP152") (pin "1") (pinfunction "1_1") (pintype "passive"))
      (node (ref "U31") (pin "38") (pinfunction "CO_38") (pintype "output"))
      (node (ref "U32") (pin "5") (pinfunction "CI_5") (pintype "input"))
    )
    (net (code "24") (name "/CO30") (class "Default")
      (node (ref "TP154") (pin "1") (pinfunction "1_1") (pintype "passive"))
      (node (ref "U32") (pin "38") (pinfunction "CO_38") (pintype "output"))
      (node (ref "U33") (pin "5") (pinfunction "CI_5") (pintype "input"))
    )
    (net (code "25") (name "/CO31") (class "Default")
      (node (ref "TP156") (pin "1") (pinfunction "1_1") (pintype "passive"))
      (node (ref "U33") (pin "38") (pinfunction "CO_38") (pintype "output"))
      (node (ref "U34") (pin "5") (pinfunction "CI_5") (pintype "input"))
    )
    (net (code "26") (name "/RI24") (class "Default")
      (node (ref "U27") (pin "6") (pinfunction "RO_6") (pintype "output"))
    )
    (net (code "27") (name "/RI25") (class "Default")
      (node (ref "TP134") (pin "1") (pinfunction "1_1") (pintype "passive"))
      (node (ref "U27") (pin "37") (pinfunction "RI_37") (pintype "input"))
      (node (ref "U28") (pin "6") (pinfunction "RO_6") (pintype "output"))
    )
    (net (code "28") (name "/RI26") (class "Default")
      (node (ref "TP136") (pin "1") (pinfunction "1_1") (pintype "passive"))
      (node (ref "U28") (pin "37") (pinfunction "RI_37") (pintype "input"))
      (node (ref "U29") (pin "6") (pinfunction "RO_6") (pintype "output"))
    )
    (net (code "29") (name "/RI27") (class "Default")
      (node (ref "TP138") (pin "1") (pinfunction "1_1") (pintype "passive"))
      (node (ref "U29") (pin "37") (pinfunction "RI_37") (pintype "input"))
      (node (ref "U30") (pin "6") (pinfunction "RO_6") (pintype "output"))
    )
    (net (code "30") (name "/RI28") (class "Default")
      (node (ref "TP140") (pin "1") (pinfunction "1_1") (pintype "passive"))
      (node (ref "U30") (pin "37") (pinfunction "RI_37") (pintype "input"))
      (node (ref "U31") (pin "6") (pinfunction "RO_6") (pintype "output"))
    )
    (net (code "31") (name "/RI29") (class "Default")
      (node (ref "TP153") (pin "1") (pinfunction "1_1") (pintype "passive"))
      (node (ref "U31") (pin "37") (pinfunction "RI_37") (pintype "input"))
      (node (ref "U32") (pin "6") (pinfunction "RO_6") (pintype "output"))
    )
    (net (code "32") (name "/RI30") (class "Default")
      (node (ref "TP155") (pin "1") (pinfunction "1_1") (pintype "passive"))
      (node (ref "U32") (pin "37") (pinfunction "RI_37") (pintype "input"))
      (node (ref "U33") (pin "6") (pinfunction "RO_6") (pintype "output"))
    )
    (net (code "33") (name "/RI31") (class "Default")
      (node (ref "TP157") (pin "1") (pinfunction "1_1") (pintype "passive"))
      (node (ref "U33") (pin "37") (pinfunction "RI_37") (pintype "input"))
      (node (ref "U34") (pin "6") (pinfunction "RO_6") (pintype "output"))
    )
    (net (code "34") (name "/RI32") (class "Default")
      (node (ref "R21") (pin "1") (pinfunction "1_1") (pintype "passive"))
      (node (ref "U34") (pin "37") (pinfunction "RI_37") (pintype "input"))
    )
    (net (code "35") (name "/RST24") (class "Default")
      (node (ref "U27") (pin "10") (pinfunction "RST_N_10") (pintype "input"))
    )
    (net (code "36") (name "/RST25") (class "Default")
      (node (ref "TP141") (pin "1") (pinfunction "1_1") (pintype "passive"))
      (node (ref "U27") (pin "33") (pinfunction "NRSTO_33") (pintype "output"))
      (node (ref "U28") (pin "10") (pinfunction "RST_N_10") (pintype "input"))
    )
    (net (code "37") (name "/RST26") (class "Default")
      (node (ref "TP143") (pin "1") (pinfunction "1_1") (pintype "passive"))
      (node (ref "U28") (pin "33") (pinfunction "NRSTO_33") (pintype "output"))
      (node (ref "U29") (pin "10") (pinfunction "RST_N_10") (pintype "input"))
    )
    (net (code "38") (name "/RST27") (class "Default")
      (node (ref "TP145") (pin "1") (pinfunction "1_1") (pintype "passive"))
      (node (ref "U29") (pin "33") (pinfunction "NRSTO_33") (pintype "output"))
      (node (ref "U30") (pin "10") (pinfunction "RST_N_10") (pintype "input"))
    )
    (net (code "39") (name "/RST28") (class "Default")
      (node (ref "TP147") (pin "1") (pinfunction "1_1") (pintype "passive"))
      (node (ref "U30") (pin "33") (pinfunction "NRSTO_33") (pintype "output"))
      (node (ref "U31") (pin "10") (pinfunction "RST_N_10") (pintype "input"))
    )
    (net (code "40") (name "/RST29") (class "Default")
      (node (ref "TP158") (pin "1") (pinfunction "1_1") (pintype "passive"))
      (node (ref "U31") (pin "33") (pinfunction "NRSTO_33") (pintype "output"))
      (node (ref "U32") (pin "10") (pinfunction "RST_N_10") (pintype "input"))
    )
    (net (code "41") (name "/RST30") (class "Default")
      (node (ref "TP160") (pin "1") (pinfunction "1_1") (pintype "passive"))
      (node (ref "U32") (pin "33") (pinfunction "NRSTO_33") (pintype "output"))
      (node (ref "U33") (pin "10") (pinfunction "RST_N_10") (pintype "input"))
    )
    (net (code "42") (name "/RST31") (class "Default")
      (node (ref "TP162") (pin "1") (pinfunction "1_1") (pintype "passive"))
      (node (ref "U33") (pin "33") (pinfunction "NRSTO_33") (pintype "output"))
      (node (ref "U34") (pin "10") (pinfunction "RST_N_10") (pintype "input"))
    )
    (net (code "43") (name "GND") (class "Default")
      (node (ref "C416") (pin "2") (pinfunction "2_2") (pintype "passive"))
      (node (ref "C417") (pin "2") (pinfunction "2_2") (pintype "passive"))
      (node (ref "C418") (pin "1") (pinfunction "1_1") (pintype "passive"))
      (node (ref "C419") (pin "1") (pinfunction "1_1") (pintype "passive"))
      (node (ref "C420") (pin "2") (pinfunction "2_2") (pintype "passive"))
      (node (ref "C421") (pin "1") (pinfunction "1_1") (pintype "passive"))
      (node (ref "C422") (pin "2") (pinfunction "2_2") (pintype "passive"))
      (node (ref "C423") (pin "1") (pinfunction "1_1") (pintype "passive"))
      (node (ref "C424") (pin "2") (pinfunction "2_2") (pintype "passive"))
      (node (ref "C425") (pin "1") (pinfunction "1_1") (pintype "passive"))
      (node (ref "C426") (pin "2") (pinfunction "2_2") (pintype "passive"))
      (node (ref "C427") (pin "1") (pinfunction "1_1") (pintype "passive"))
      (node (ref "C428") (pin "1") (pinfunction "1_1") (pintype "passive"))
      (node (ref "C429") (pin "1") (pinfunction "1_1") (pintype "passive"))
      (node (ref "C430") (pin "1") (pinfunction "1_1") (pintype "passive"))
      (node (ref "C431") (pin "1") (pinfunction "1_1") (pintype "passive"))
      (node (ref "C432") (pin "1") (pinfunction "1_1") (pintype "passive"))
      (node (ref "C433") (pin "1") (pinfunction "1_1") (pintype "passive"))
      (node (ref "C434") (pin "1") (pinfunction "1_1") (pintype "passive"))
      (node (ref "C435") (pin "1") (pinfunction "1_1") (pintype "passive"))
      (node (ref "C436") (pin "1") (pinfunction "1_1") (pintype "passive"))
      (node (ref "C437") (pin "1") (pinfunction "1_1") (pintype "passive"))
      (node (ref "C438") (pin "1") (pinfunction "1_1") (pintype "passive"))
      (node (ref "C439") (pin "1") (pinfunction "1_1") (pintype "passive"))
      (node (ref "C440") (pin "1") (pinfunction "1_1") (pintype "passive"))
      (node (ref "C441") (pin "1") (pinfunction "1_1") (pintype "passive"))
      (node (ref "C442") (pin "1") (pinfunction "1_1") (pintype "passive"))
      (node (ref "C443") (pin "1") (pinfunction "1_1") (pintype "passive"))
      (node (ref "C444") (pin "1") (pinfunction "1_1") (pintype "passive"))
      (node (ref "C445") (pin "1") (pinfunction "1_1") (pintype "passive"))
      (node (ref "C446") (pin "1") (pinfunction "1_1") (pintype "passive"))
      (node (ref "C447") (pin "1") (pinfunction "1_1") (pintype "passive"))
      (node (ref "C448") (pin "1") (pinfunction "1_1") (pintype "passive"))
      (node (ref "C449") (pin "1") (pinfunction "1_1") (pintype "passive"))
      (node (ref "C450") (pin "1") (pinfunction "1_1") (pintype "passive"))
      (node (ref "C451") (pin "1") (pinfunction "1_1") (pintype "passive"))
      (node (ref "C452") (pin "1") (pinfunction "1_1") (pintype "passive"))
      (node (ref "C453") (pin "1") (pinfunction "1_1") (pintype "passive"))
      (node (ref "C454") (pin "1") (pinfunction "1_1") (pintype "passive"))
      (node (ref "C455") (pin "1") (pinfunction "1_1") (pintype "passive"))
      (node (ref "C456") (pin "1") (pinfunction "1_1") (pintype "passive"))
      (node (ref "C457") (pin "1") (pinfunction "1_1") (pintype "passive"))
      (node (ref "C458") (pin "1") (pinfunction "1_1") (pintype "passive"))
      (node (ref "C459") (pin "1") (pinfunction "1_1") (pintype "passive"))
      (node (ref "C460") (pin "1") (pinfunction "1_1") (pintype "passive"))
      (node (ref "C461") (pin "1") (pinfunction "1_1") (pintype "passive"))
      (node (ref "C462") (pin "1") (pinfunction "1_1") (pintype "passive"))
      (node (ref "C463") (pin "1") (pinfunction "1_1") (pintype "passive"))
      (node (ref "C464") (pin "1") (pinfunction "1_1") (pintype "passive"))
      (node (ref "C465") (pin "1") (pinfunction "1_1") (pintype "passive"))
      (node (ref "C466") (pin "1") (pinfunction "1_1") (pintype "passive"))
      (node (ref "C467") (pin "1") (pinfunction "1_1") (pintype "passive"))
      (node (ref "C468") (pin "1") (pinfunction "1_1") (pintype "passive"))
      (node (ref "C469") (pin "1") (pinfunction "1_1") (pintype "passive"))
      (node (ref "C470") (pin "1") (pinfunction "1_1") (pintype "passive"))
      (node (ref "C471") (pin "1") (pinfunction "1_1") (pintype "passive"))
      (node (ref "C472") (pin "1") (pinfunction "1_1") (pintype "passive"))
      (node (ref "C473") (pin "1") (pinfunction "1_1") (pintype "passive"))
      (node (ref "C474") (pin "1") (pinfunction "1_1") (pintype "passive"))
      (node (ref "C475") (pin "1") (pinfunction "1_1") (pintype "passive"))
      (node (ref "C476") (pin "1") (pinfunction "1_1") (pintype "passive"))
      (node (ref "C477") (pin "1") (pinfunction "1_1") (pintype "passive"))
      (node (ref "C478") (pin "1") (pinfunction "1_1") (pintype "passive"))
      (node (ref "C479") (pin "1") (pinfunction "1_1") (pintype "passive"))
      (node (ref "C480") (pin "1") (pinfunction "1_1") (pintype "passive"))
      (node (ref "C481") (pin "1") (pinfunction "1_1") (pintype "passive"))
      (node (ref "C482") (pin "1") (pinfunction "1_1") (pintype "passive"))
      (node (ref "C483") (pin "1") (pinfunction "1_1") (pintype "passive"))
      (node (ref "C484") (pin "2") (pinfunction "2_2") (pintype "passive"))
      (node (ref "C485") (pin "1") (pinfunction "1_1") (pintype "passive"))
      (node (ref "C486") (pin "2") (pinfunction "2_2") (pintype "passive"))
      (node (ref "C487") (pin "1") (pinfunction "1_1") (pintype "passive"))
      (node (ref "C488") (pin "2") (pinfunction "2_2") (pintype "passive"))
      (node (ref "C489") (pin "1") (pinfunction "1_1") (pintype "passive"))
      (node (ref "C490") (pin "2") (pinfunction "2_2") (pintype "passive"))
      (node (ref "C491") (pin "1") (pinfunction "1_1") (pintype "passive"))
      (node (ref "C492") (pin "1") (pinfunction "1_1") (pintype "passive"))
      (node (ref "C493") (pin "1") (pinfunction "1_1") (pintype "passive"))
      (node (ref "C494") (pin "1") (pinfunction "1_1") (pintype "passive"))
      (node (ref "C495") (pin "1") (pinfunction "1_1") (pintype "passive"))
      (node (ref "C496") (pin "1") (pinfunction "1_1") (pintype "passive"))
      (node (ref "C497") (pin "1") (pinfunction "1_1") (pintype "passive"))
      (node (ref "C498") (pin "1") (pinfunction "1_1") (pintype "passive"))
      (node (ref "C499") (pin "1") (pinfunction "1_1") (pintype "passive"))
      (node (ref "C500") (pin "1") (pinfunction "1_1") (pintype "passive"))
      (node (ref "C501") (pin "1") (pinfunction "1_1") (pintype "passive"))
      (node (ref "C502") (pin "1") (pinfunction "1_1") (pintype "passive"))
      (node (ref "C503") (pin "1") (pinfunction "1_1") (pintype "passive"))
      (node (ref "C504") (pin "1") (pinfunction "1_1") (pintype "passive"))
      (node (ref "C505") (pin "1") (pinfunction "1_1") (pintype "passive"))
      (node (ref "C506") (pin "1") (pinfunction "1_1") (pintype "passive"))
      (node (ref "C507") (pin "1") (pinfunction "1_1") (pintype "passive"))
      (node (ref "C508") (pin "1") (pinfunction "1_1") (pintype "passive"))
      (node (ref "C509") (pin "1") (pinfunction "1_1") (pintype "passive"))
      (node (ref "C510") (pin "1") (pinfunction "1_1") (pintype "passive"))
      (node (ref "C511") (pin "1") (pinfunction "1_1") (pintype "passive"))
      (node (ref "C512") (pin "1") (pinfunction "1_1") (pintype "passive"))
      (node (ref "C513") (pin "1") (pinfunction "1_1") (pintype "passive"))
      (node (ref "C514") (pin "1") (pinfunction "1_1") (pintype "passive"))
      (node (ref "C515") (pin "1") (pinfunction "1_1") (pintype "passive"))
      (node (ref "C516") (pin "1") (pinfunction "1_1") (pintype "passive"))
      (node (ref "C517") (pin "1") (pinfunction "1_1") (pintype "passive"))
      (node (ref "C518") (pin "1") (pinfunction "1_1") (pintype "passive"))
      (node (ref "C519") (pin "1") (pinfunction "1_1") (pintype "passive"))
      (node (ref "C520") (pin "1") (pinfunction "1_1") (pintype "passive"))
      (node (ref "C521") (pin "1") (pinfunction "1_1") (pintype "passive"))
      (node (ref "C522") (pin "1") (pinfunction "1_1") (pintype "passive"))
      (node (ref "C523") (pin "1") (pinfunction "1_1") (pintype "passive"))
      (node (ref "C524") (pin "1") (pinfunction "1_1") (pintype "passive"))
      (node (ref "C525") (pin "1") (pinfunction "1_1") (pintype "passive"))
      (node (ref "C526") (pin "1") (pinfunction "1_1") (pintype "passive"))
      (node (ref "C527") (pin "1") (pinfunction "1_1") (pintype "passive"))
      (node (ref "C528") (pin "1") (pinfunction "1_1") (pintype "passive"))
      (node (ref "C529") (pin "1") (pinfunction "1_1") (pintype "passive"))
      (node (ref "C530") (pin "1") (pinfunction "1_1") (pintype "passive"))
      (node (ref "C531") (pin "1") (pinfunction "1_1") (pintype "passive"))
      (node (ref "C532") (pin "1") (pinfunction "1_1") (pintype "passive"))
      (node (ref "C533") (pin "1") (pinfunction "1_1") (pintype "passive"))
      (node (ref "C534") (pin "1") (pinfunction "1_1") (pintype "passive"))
      (node (ref "C535") (pin "1") (pinfunction "1_1") (pintype "passive"))
      (node (ref "C536") (pin "1") (pinfunction "1_1") (pintype "passive"))
      (node (ref "C537") (pin "1") (pinfunction "1_1") (pintype "passive"))
      (node (ref "C538") (pin "1") (pinfunction "1_1") (pintype "passive"))
      (node (ref "C539") (pin "1") (pinfunction "1_1") (pintype "passive"))
      (node (ref "C540") (pin "1") (pinfunction "1_1") (pintype "passive"))
      (node (ref "C541") (pin "1") (pinfunction "1_1") (pintype "passive"))
      (node (ref "C542") (pin "1") (pinfunction "1_1") (pintype "passive"))
      (node (ref "C543") (pin "1") (pinfunction "1_1") (pintype "passive"))
      (node (ref "C544") (pin "1") (pinfunction "1_1") (pintype "passive"))
      (node (ref "C545") (pin "1") (pinfunction "1_1") (pintype "passive"))
      (node (ref "C546") (pin "1") (pinfunction "1_1") (pintype "passive"))
      (node (ref "C547") (pin "1") (pinfunction "1_1") (pintype "passive"))
      (node (ref "M19") (pin "0") (pinfunction "PIN_0") (pintype "power_in"))
      (node (ref "M20") (pin "0") (pinfunction "PIN_0") (pintype "power_in"))
      (node (ref "M21") (pin "0") (pinfunction "PIN_0") (pintype "power_in"))
      (node (ref "M22") (pin "0") (pinfunction "PIN_0") (pintype "power_in"))
      (node (ref "M23") (pin "0") (pinfunction "PIN_0") (pintype "power_in"))
      (node (ref "R19") (pin "1") (pinfunction "1_1") (pintype "passive"))
      (node (ref "R20") (pin "1") (pinfunction "1_1") (pintype "passive"))
      (node (ref "U27") (pin "12") (pinfunction "GND_12") (pintype "power_in"))
      (node (ref "U27") (pin "13") (pinfunction "VSS_13") (pintype "power_in"))
      (node (ref "U27") (pin "15") (pinfunction "ADDR0_15") (pintype "passive"))
      (node (ref "U27") (pin "16") (pinfunction "ADDR1_16") (pintype "passive"))
      (node (ref "U27") (pin "18") (pinfunction "GND_18") (pintype "power_in"))
      (node (ref "U27") (pin "19") (pinfunction "ADDR2_19") (pintype "passive"))
      (node (ref "U27") (pin "20") (pinfunction "ADDR3_20") (pintype "passive"))
      (node (ref "U27") (pin "22") (pinfunction "GND_22") (pintype "power_in"))
      (node (ref "U27") (pin "23") (pinfunction "ADDR4_23") (pintype "passive"))
      (node (ref "U27") (pin "24") (pinfunction "ADDR5_24") (pintype "passive"))
      (node (ref "U27") (pin "26") (pinfunction "GND_26") (pintype "power_in"))
      (node (ref "U27") (pin "3") (pinfunction "GND_3") (pintype "power_in"))
      (node (ref "U27") (pin "30") (pinfunction "VSS_30") (pintype "power_in"))
      (node (ref "U27") (pin "31") (pinfunction "GND_31") (pintype "power_in"))
      (node (ref "U27") (pin "35") (pinfunction "GND_35") (pintype "power_in"))
      (node (ref "U27") (pin "41") (pinfunction "GND_41") (pintype "power_in"))
      (node (ref "U27") (pin "42") (pinfunction "VSS_42") (pintype "power_in"))
      (node (ref "U27") (pin "45") (pinfunction "SMODE_45") (pintype "passive"))
      (node (ref "U27") (pin "46") (pinfunction "GND_46") (pintype "power_in"))
      (node (ref "U27") (pin "50") (pinfunction "TEST_50") (pintype "passive"))
      (node (ref "U27") (pin "52") (pinfunction "GND_52") (pintype "power_in"))
      (node (ref "U27") (pin "53") (pinfunction "PLL_DVSS_53") (pintype "power_in"))
      (node (ref "U27") (pin "56") (pinfunction "PLL_AVSS_56") (pintype "power_in"))
      (node (ref "U27") (pin "57") (pinfunction "GND_57") (pintype "power_in"))
      (node (ref "U27") (pin "8") (pinfunction "GND_8") (pintype "power_in"))
      (node (ref "U28") (pin "12") (pinfunction "GND_12") (pintype "power_in"))
      (node (ref "U28") (pin "13") (pinfunction "VSS_13") (pintype "power_in"))
      (node (ref "U28") (pin "15") (pinfunction "ADDR0_15") (pintype "passive"))
      (node (ref "U28") (pin "16") (pinfunction "ADDR1_16") (pintype "passive"))
      (node (ref "U28") (pin "18") (pinfunction "GND_18") (pintype "power_in"))
      (node (ref "U28") (pin "19") (pinfunction "ADDR2_19") (pintype "passive"))
      (node (ref "U28") (pin "22") (pinfunction "GND_22") (pintype "power_in"))
      (node (ref "U28") (pin "23") (pinfunction "ADDR4_23") (pintype "passive"))
      (node (ref "U28") (pin "24") (pinfunction "ADDR5_24") (pintype "passive"))
      (node (ref "U28") (pin "26") (pinfunction "GND_26") (pintype "power_in"))
      (node (ref "U28") (pin "3") (pinfunction "GND_3") (pintype "power_in"))
      (node (ref "U28") (pin "30") (pinfunction "VSS_30") (pintype "power_in"))
      (node (ref "U28") (pin "31") (pinfunction "GND_31") (pintype "power_in"))
      (node (ref "U28") (pin "35") (pinfunction "GND_35") (pintype "power_in"))
      (node (ref "U28") (pin "41") (pinfunction "GND_41") (pintype "power_in"))
      (node (ref "U28") (pin "42") (pinfunction "VSS_42") (pintype "power_in"))
      (node (ref "U28") (pin "45") (pinfunction "SMODE_45") (pintype "passive"))
      (node (ref "U28") (pin "46") (pinfunction "GND_46") (pintype "power_in"))
      (node (ref "U28") (pin "50") (pinfunction "TEST_50") (pintype "passive"))
      (node (ref "U28") (pin "52") (pinfunction "GND_52") (pintype "power_in"))
      (node (ref "U28") (pin "53") (pinfunction "PLL_DVSS_53") (pintype "power_in"))
      (node (ref "U28") (pin "56") (pinfunction "PLL_AVSS_56") (pintype "power_in"))
      (node (ref "U28") (pin "57") (pinfunction "GND_57") (pintype "power_in"))
      (node (ref "U28") (pin "8") (pinfunction "GND_8") (pintype "power_in"))
      (node (ref "U29") (pin "12") (pinfunction "GND_12") (pintype "power_in"))
      (node (ref "U29") (pin "13") (pinfunction "VSS_13") (pintype "power_in"))
      (node (ref "U29") (pin "15") (pinfunction "ADDR0_15") (pintype "passive"))
      (node (ref "U29") (pin "16") (pinfunction "ADDR1_16") (pintype "passive"))
      (node (ref "U29") (pin "18") (pinfunction "GND_18") (pintype "power_in"))
      (node (ref "U29") (pin "19") (pinfunction "ADDR2_19") (pintype "passive"))
      (node (ref "U29") (pin "20") (pinfunction "ADDR3_20") (pintype "passive"))
      (node (ref "U29") (pin "22") (pinfunction "GND_22") (pintype "power_in"))
      (node (ref "U29") (pin "24") (pinfunction "ADDR5_24") (pintype "passive"))
      (node (ref "U29") (pin "26") (pinfunction "GND_26") (pintype "power_in"))
      (node (ref "U29") (pin "3") (pinfunction "GND_3") (pintype "power_in"))
      (node (ref "U29") (pin "30") (pinfunction "VSS_30") (pintype "power_in"))
      (node (ref "U29") (pin "31") (pinfunction "GND_31") (pintype "power_in"))
      (node (ref "U29") (pin "35") (pinfunction "GND_35") (pintype "power_in"))
      (node (ref "U29") (pin "41") (pinfunction "GND_41") (pintype "power_in"))
      (node (ref "U29") (pin "42") (pinfunction "VSS_42") (pintype "power_in"))
      (node (ref "U29") (pin "45") (pinfunction "SMODE_45") (pintype "passive"))
      (node (ref "U29") (pin "46") (pinfunction "GND_46") (pintype "power_in"))
      (node (ref "U29") (pin "50") (pinfunction "TEST_50") (pintype "passive"))
      (node (ref "U29") (pin "52") (pinfunction "GND_52") (pintype "power_in"))
      (node (ref "U29") (pin "53") (pinfunction "PLL_DVSS_53") (pintype "power_in"))
      (node (ref "U29") (pin "56") (pinfunction "PLL_AVSS_56") (pintype "power_in"))
      (node (ref "U29") (pin "57") (pinfunction "GND_57") (pintype "power_in"))
      (node (ref "U29") (pin "8") (pinfunction "GND_8") (pintype "power_in"))
      (node (ref "U30") (pin "12") (pinfunction "GND_12") (pintype "power_in"))
      (node (ref "U30") (pin "13") (pinfunction "VSS_13") (pintype "power_in"))
      (node (ref "U30") (pin "15") (pinfunction "ADDR0_15") (pintype "passive"))
      (node (ref "U30") (pin "16") (pinfunction "ADDR1_16") (pintype "passive"))
      (node (ref "U30") (pin "18") (pinfunction "GND_18") (pintype "power_in"))
      (node (ref "U30") (pin "19") (pinfunction "ADDR2_19") (pintype "passive"))
      (node (ref "U30") (pin "22") (pinfunction "GND_22") (pintype "power_in"))
      (node (ref "U30") (pin "24") (pinfunction "ADDR5_24") (pintype "passive"))
      (node (ref "U30") (pin "26") (pinfunction "GND_26") (pintype "power_in"))
      (node (ref "U30") (pin "3") (pinfunction "GND_3") (pintype "power_in"))
      (node (ref "U30") (pin "30") (pinfunction "VSS_30") (pintype "power_in"))
      (node (ref "U30") (pin "31") (pinfunction "GND_31") (pintype "power_in"))
      (node (ref "U30") (pin "35") (pinfunction "GND_35") (pintype "power_in"))
      (node (ref "U30") (pin "41") (pinfunction "GND_41") (pintype "power_in"))
      (node (ref "U30") (pin "42") (pinfunction "VSS_42") (pintype "power_in"))
      (node (ref "U30") (pin "45") (pinfunction "SMODE_45") (pintype "passive"))
      (node (ref "U30") (pin "46") (pinfunction "GND_46") (pintype "power_in"))
      (node (ref "U30") (pin "50") (pinfunction "TEST_50") (pintype "passive"))
      (node (ref "U30") (pin "52") (pinfunction "GND_52") (pintype "power_in"))
      (node (ref "U30") (pin "53") (pinfunction "PLL_DVSS_53") (pintype "power_in"))
      (node (ref "U30") (pin "56") (pinfunction "PLL_AVSS_56") (pintype "power_in"))
      (node (ref "U30") (pin "57") (pinfunction "GND_57") (pintype "power_in"))
      (node (ref "U30") (pin "8") (pinfunction "GND_8") (pintype "power_in"))
      (node (ref "U31") (pin "12") (pinfunction "GND_12") (pintype "power_in"))
      (node (ref "U31") (pin "13") (pinfunction "VSS_13") (pintype "power_in"))
      (node (ref "U31") (pin "15") (pinfunction "ADDR0_15") (pintype "passive"))
      (node (ref "U31") (pin "16") (pinfunction "ADDR1_16") (pintype "passive"))
      (node (ref "U31") (pin "18") (pinfunction "GND_18") (pintype "power_in"))
      (node (ref "U31") (pin "19") (pinfunction "ADDR2_19") (pintype "passive"))
      (node (ref "U31") (pin "20") (pinfunction "ADDR3_20") (pintype "passive"))
      (node (ref "U31") (pin "22") (pinfunction "GND_22") (pintype "power_in"))
      (node (ref "U31") (pin "23") (pinfunction "ADDR4_23") (pintype "passive"))
      (node (ref "U31") (pin "26") (pinfunction "GND_26") (pintype "power_in"))
      (node (ref "U31") (pin "3") (pinfunction "GND_3") (pintype "power_in"))
      (node (ref "U31") (pin "30") (pinfunction "VSS_30") (pintype "power_in"))
      (node (ref "U31") (pin "31") (pinfunction "GND_31") (pintype "power_in"))
      (node (ref "U31") (pin "35") (pinfunction "GND_35") (pintype "power_in"))
      (node (ref "U31") (pin "41") (pinfunction "GND_41") (pintype "power_in"))
      (node (ref "U31") (pin "42") (pinfunction "VSS_42") (pintype "power_in"))
      (node (ref "U31") (pin "45") (pinfunction "SMODE_45") (pintype "passive"))
      (node (ref "U31") (pin "46") (pinfunction "GND_46") (pintype "power_in"))
      (node (ref "U31") (pin "50") (pinfunction "TEST_50") (pintype "passive"))
      (node (ref "U31") (pin "52") (pinfunction "GND_52") (pintype "power_in"))
      (node (ref "U31") (pin "53") (pinfunction "PLL_DVSS_53") (pintype "power_in"))
      (node (ref "U31") (pin "56") (pinfunction "PLL_AVSS_56") (pintype "power_in"))
      (node (ref "U31") (pin "57") (pinfunction "GND_57") (pintype "power_in"))
      (node (ref "U31") (pin "8") (pinfunction "GND_8") (pintype "power_in"))
      (node (ref "U32") (pin "12") (pinfunction "GND_12") (pintype "power_in"))
      (node (ref "U32") (pin "13") (pinfunction "VSS_13") (pintype "power_in"))
      (node (ref "U32") (pin "15") (pinfunction "ADDR0_15") (pintype "passive"))
      (node (ref "U32") (pin "16") (pinfunction "ADDR1_16") (pintype "passive"))
      (node (ref "U32") (pin "18") (pinfunction "GND_18") (pintype "power_in"))
      (node (ref "U32") (pin "19") (pinfunction "ADDR2_19") (pintype "passive"))
      (node (ref "U32") (pin "22") (pinfunction "GND_22") (pintype "power_in"))
      (node (ref "U32") (pin "23") (pinfunction "ADDR4_23") (pintype "passive"))
      (node (ref "U32") (pin "26") (pinfunction "GND_26") (pintype "power_in"))
      (node (ref "U32") (pin "3") (pinfunction "GND_3") (pintype "power_in"))
      (node (ref "U32") (pin "30") (pinfunction "VSS_30") (pintype "power_in"))
      (node (ref "U32") (pin "31") (pinfunction "GND_31") (pintype "power_in"))
      (node (ref "U32") (pin "35") (pinfunction "GND_35") (pintype "power_in"))
      (node (ref "U32") (pin "41") (pinfunction "GND_41") (pintype "power_in"))
      (node (ref "U32") (pin "42") (pinfunction "VSS_42") (pintype "power_in"))
      (node (ref "U32") (pin "45") (pinfunction "SMODE_45") (pintype "passive"))
      (node (ref "U32") (pin "46") (pinfunction "GND_46") (pintype "power_in"))
      (node (ref "U32") (pin "50") (pinfunction "TEST_50") (pintype "passive"))
      (node (ref "U32") (pin "52") (pinfunction "GND_52") (pintype "power_in"))
      (node (ref "U32") (pin "53") (pinfunction "PLL_DVSS_53") (pintype "power_in"))
      (node (ref "U32") (pin "56") (pinfunction "PLL_AVSS_56") (pintype "power_in"))
      (node (ref "U32") (pin "57") (pinfunction "GND_57") (pintype "power_in"))
      (node (ref "U32") (pin "8") (pinfunction "GND_8") (pintype "power_in"))
      (node (ref "U33") (pin "12") (pinfunction "GND_12") (pintype "power_in"))
      (node (ref "U33") (pin "13") (pinfunction "VSS_13") (pintype "power_in"))
      (node (ref "U33") (pin "15") (pinfunction "ADDR0_15") (pintype "passive"))
      (node (ref "U33") (pin "16") (pinfunction "ADDR1_16") (pintype "passive"))
      (node (ref "U33") (pin "18") (pinfunction "GND_18") (pintype "power_in"))
      (node (ref "U33") (pin "19") (pinfunction "ADDR2_19") (pintype "passive"))
      (node (ref "U33") (pin "20") (pinfunction "ADDR3_20") (pintype "passive"))
      (node (ref "U33") (pin "22") (pinfunction "GND_22") (pintype "power_in"))
      (node (ref "U33") (pin "26") (pinfunction "GND_26") (pintype "power_in"))
      (node (ref "U33") (pin "3") (pinfunction "GND_3") (pintype "power_in"))
      (node (ref "U33") (pin "30") (pinfunction "VSS_30") (pintype "power_in"))
      (node (ref "U33") (pin "31") (pinfunction "GND_31") (pintype "power_in"))
      (node (ref "U33") (pin "35") (pinfunction "GND_35") (pintype "power_in"))
      (node (ref "U33") (pin "41") (pinfunction "GND_41") (pintype "power_in"))
      (node (ref "U33") (pin "42") (pinfunction "VSS_42") (pintype "power_in"))
      (node (ref "U33") (pin "45") (pinfunction "SMODE_45") (pintype "passive"))
      (node (ref "U33") (pin "46") (pinfunction "GND_46") (pintype "power_in"))
      (node (ref "U33") (pin "50") (pinfunction "TEST_50") (pintype "passive"))
      (node (ref "U33") (pin "52") (pinfunction "GND_52") (pintype "power_in"))
      (node (ref "U33") (pin "53") (pinfunction "PLL_DVSS_53") (pintype "power_in"))
      (node (ref "U33") (pin "56") (pinfunction "PLL_AVSS_56") (pintype "power_in"))
      (node (ref "U33") (pin "57") (pinfunction "GND_57") (pintype "power_in"))
      (node (ref "U33") (pin "8") (pinfunction "GND_8") (pintype "power_in"))
      (node (ref "U34") (pin "12") (pinfunction "GND_12") (pintype "power_in"))
      (node (ref "U34") (pin "13") (pinfunction "VSS_13") (pintype "power_in"))
      (node (ref "U34") (pin "15") (pinfunction "ADDR0_15") (pintype "passive"))
      (node (ref "U34") (pin "16") (pinfunction "ADDR1_16") (pintype "passive"))
      (node (ref "U34") (pin "18") (pinfunction "GND_18") (pintype "power_in"))
      (node (ref "U34") (pin "19") (pinfunction "ADDR2_19") (pintype "passive"))
      (node (ref "U34") (pin "22") (pinfunction "GND_22") (pintype "power_in"))
      (node (ref "U34") (pin "26") (pinfunction "GND_26") (pintype "power_in"))
      (node (ref "U34") (pin "3") (pinfunction "GND_3") (pintype "power_in"))
      (node (ref "U34") (pin "30") (pinfunction "VSS_30") (pintype "power_in"))
      (node (ref "U34") (pin "31") (pinfunction "GND_31") (pintype "power_in"))
      (node (ref "U34") (pin "35") (pinfunction "GND_35") (pintype "power_in"))
      (node (ref "U34") (pin "41") (pinfunction "GND_41") (pintype "power_in"))
      (node (ref "U34") (pin "42") (pinfunction "VSS_42") (pintype "power_in"))
      (node (ref "U34") (pin "45") (pinfunction "SMODE_45") (pintype "passive"))
      (node (ref "U34") (pin "46") (pinfunction "GND_46") (pintype "power_in"))
      (node (ref "U34") (pin "50") (pinfunction "TEST_50") (pintype "passive"))
      (node (ref "U34") (pin "52") (pinfunction "GND_52") (pintype "power_in"))
      (node (ref "U34") (pin "53") (pinfunction "PLL_DVSS_53") (pintype "power_in"))
      (node (ref "U34") (pin "56") (pinfunction "PLL_AVSS_56") (pintype "power_in"))
      (node (ref "U34") (pin "57") (pinfunction "GND_57") (pintype "power_in"))
      (node (ref "U34") (pin "8") (pinfunction "GND_8") (pintype "power_in"))
    )
    (net (code "44") (name "Net-(RF-A)") (class "Default")
      (node (ref "RF") (pin "1") (pinfunction "A_1") (pintype "passive"))
      (node (ref "U34") (pin "49") (pinfunction "RF_49") (pintype "output"))
    )
    (net (code "45") (name "Net-(RF-K)") (class "Default")
      (node (ref "R20") (pin "2") (pinfunction "2_2") (pintype "passive"))
      (node (ref "RF") (pin "2") (pinfunction "K_2") (pintype "passive"))
    )
    (net (code "46") (name "Net-(TF-A)") (class "Default")
      (node (ref "TF") (pin "1") (pinfunction "A_1") (pintype "passive"))
      (node (ref "U34") (pin "48") (pinfunction "TF_48") (pintype "output"))
    )
    (net (code "47") (name "Net-(TF-K)") (class "Default")
      (node (ref "R19") (pin "2") (pinfunction "2_2") (pintype "passive"))
      (node (ref "TF") (pin "2") (pinfunction "K_2") (pintype "passive"))
    )
    (net (code "48") (name "Net-(U27-PLL_AVDD)") (class "Default")
      (node (ref "C421") (pin "2") (pinfunction "2_2") (pintype "passive"))
      (node (ref "FB25") (pin "1") (pinfunction "1_1") (pintype "passive"))
      (node (ref "U27") (pin "55") (pinfunction "PLL_AVDD_55") (pintype "power_in"))
    )
    (net (code "49") (name "Net-(U28-PLL_AVDD)") (class "Default")
      (node (ref "C423") (pin "2") (pinfunction "2_2") (pintype "passive"))
      (node (ref "FB26") (pin "1") (pinfunction "1_1") (pintype "passive"))
      (node (ref "U28") (pin "55") (pinfunction "PLL_AVDD_55") (pintype "power_in"))
    )
    (net (code "50") (name "Net-(U29-PLL_AVDD)") (class "Default")
      (node (ref "C425") (pin "2") (pinfunction "2_2") (pintype "passive"))
      (node (ref "FB27") (pin "1") (pinfunction "1_1") (pintype "passive"))
      (node (ref "U29") (pin "55") (pinfunction "PLL_AVDD_55") (pintype "power_in"))
    )
    (net (code "51") (name "Net-(U30-PLL_AVDD)") (class "Default")
      (node (ref "C427") (pin "2") (pinfunction "2_2") (pintype "passive"))
      (node (ref "FB28") (pin "1") (pinfunction "1_1") (pintype "passive"))
      (node (ref "U30") (pin "55") (pinfunction "PLL_AVDD_55") (pintype "power_in"))
    )
    (net (code "52") (name "Net-(U31-PLL_AVDD)") (class "Default")
      (node (ref "C485") (pin "2") (pinfunction "2_2") (pintype "passive"))
      (node (ref "FB29") (pin "1") (pinfunction "1_1") (pintype "passive"))
      (node (ref "U31") (pin "55") (pinfunction "PLL_AVDD_55") (pintype "power_in"))
    )
    (net (code "53") (name "Net-(U32-PLL_AVDD)") (class "Default")
      (node (ref "C487") (pin "2") (pinfunction "2_2") (pintype "passive"))
      (node (ref "FB30") (pin "1") (pinfunction "1_1") (pintype "passive"))
      (node (ref "U32") (pin "55") (pinfunction "PLL_AVDD_55") (pintype "power_in"))
    )
    (net (code "54") (name "Net-(U33-PLL_AVDD)") (class "Default")
      (node (ref "C489") (pin "2") (pinfunction "2_2") (pintype "passive"))
      (node (ref "FB31") (pin "1") (pinfunction "1_1") (pintype "passive"))
      (node (ref "U33") (pin "55") (pinfunction "PLL_AVDD_55") (pintype "power_in"))
    )
    (net (code "55") (name "Net-(U34-PLL_AVDD)") (class "Default")
      (node (ref "C491") (pin "2") (pinfunction "2_2") (pintype "passive"))
      (node (ref "FB32") (pin "1") (pinfunction "1_1") (pintype "passive"))
      (node (ref "U34") (pin "55") (pinfunction "PLL_AVDD_55") (pintype "power_in"))
    )
    (net (code "56") (name "VDD4") (class "Default")
      (node (ref "C416") (pin "1") (pinfunction "1_1") (pintype "passive"))
      (node (ref "C417") (pin "1") (pinfunction "1_1") (pintype "passive"))
      (node (ref "C418") (pin "2") (pinfunction "2_2") (pintype "passive"))
      (node (ref "C419") (pin "2") (pinfunction "2_2") (pintype "passive"))
      (node (ref "C440") (pin "2") (pinfunction "2_2") (pintype "passive"))
      (node (ref "C441") (pin "2") (pinfunction "2_2") (pintype "passive"))
      (node (ref "C442") (pin "2") (pinfunction "2_2") (pintype "passive"))
      (node (ref "C443") (pin "2") (pinfunction "2_2") (pintype "passive"))
      (node (ref "C444") (pin "2") (pinfunction "2_2") (pintype "passive"))
      (node (ref "C445") (pin "2") (pinfunction "2_2") (pintype "passive"))
      (node (ref "C446") (pin "2") (pinfunction "2_2") (pintype "passive"))
      (node (ref "C447") (pin "2") (pinfunction "2_2") (pintype "passive"))
      (node (ref "C448") (pin "2") (pinfunction "2_2") (pintype "passive"))
      (node (ref "C449") (pin "2") (pinfunction "2_2") (pintype "passive"))
      (node (ref "C450") (pin "2") (pinfunction "2_2") (pintype "passive"))
      (node (ref "C451") (pin "2") (pinfunction "2_2") (pintype "passive"))
      (node (ref "C452") (pin "2") (pinfunction "2_2") (pintype "passive"))
      (node (ref "C453") (pin "2") (pinfunction "2_2") (pintype "passive"))
      (node (ref "C454") (pin "2") (pinfunction "2_2") (pintype "passive"))
      (node (ref "C455") (pin "2") (pinfunction "2_2") (pintype "passive"))
      (node (ref "C456") (pin "2") (pinfunction "2_2") (pintype "passive"))
      (node (ref "C457") (pin "2") (pinfunction "2_2") (pintype "passive"))
      (node (ref "C458") (pin "2") (pinfunction "2_2") (pintype "passive"))
      (node (ref "C459") (pin "2") (pinfunction "2_2") (pintype "passive"))
      (node (ref "C460") (pin "2") (pinfunction "2_2") (pintype "passive"))
      (node (ref "C461") (pin "2") (pinfunction "2_2") (pintype "passive"))
      (node (ref "C462") (pin "2") (pinfunction "2_2") (pintype "passive"))
      (node (ref "C463") (pin "2") (pinfunction "2_2") (pintype "passive"))
      (node (ref "C464") (pin "2") (pinfunction "2_2") (pintype "passive"))
      (node (ref "C465") (pin "2") (pinfunction "2_2") (pintype "passive"))
      (node (ref "C466") (pin "2") (pinfunction "2_2") (pintype "passive"))
      (node (ref "C467") (pin "2") (pinfunction "2_2") (pintype "passive"))
      (node (ref "C468") (pin "2") (pinfunction "2_2") (pintype "passive"))
      (node (ref "C469") (pin "2") (pinfunction "2_2") (pintype "passive"))
      (node (ref "C470") (pin "2") (pinfunction "2_2") (pintype "passive"))
      (node (ref "C471") (pin "2") (pinfunction "2_2") (pintype "passive"))
      (node (ref "C472") (pin "2") (pinfunction "2_2") (pintype "passive"))
      (node (ref "C473") (pin "2") (pinfunction "2_2") (pintype "passive"))
      (node (ref "C474") (pin "2") (pinfunction "2_2") (pintype "passive"))
      (node (ref "C475") (pin "2") (pinfunction "2_2") (pintype "passive"))
      (node (ref "C476") (pin "2") (pinfunction "2_2") (pintype "passive"))
      (node (ref "C477") (pin "2") (pinfunction "2_2") (pintype "passive"))
      (node (ref "C478") (pin "2") (pinfunction "2_2") (pintype "passive"))
      (node (ref "C479") (pin "2") (pinfunction "2_2") (pintype "passive"))
      (node (ref "C480") (pin "2") (pinfunction "2_2") (pintype "passive"))
      (node (ref "C481") (pin "2") (pinfunction "2_2") (pintype "passive"))
      (node (ref "C482") (pin "2") (pinfunction "2_2") (pintype "passive"))
      (node (ref "C483") (pin "2") (pinfunction "2_2") (pintype "passive"))
      (node (ref "C504") (pin "2") (pinfunction "2_2") (pintype "passive"))
      (node (ref "C505") (pin "2") (pinfunction "2_2") (pintype "passive"))
      (node (ref "C506") (pin "2") (pinfunction "2_2") (pintype "passive"))
      (node (ref "C507") (pin "2") (pinfunction "2_2") (pintype "passive"))
      (node (ref "C508") (pin "2") (pinfunction "2_2") (pintype "passive"))
      (node (ref "C509") (pin "2") (pinfunction "2_2") (pintype "passive"))
      (node (ref "C510") (pin "2") (pinfunction "2_2") (pintype "passive"))
      (node (ref "C511") (pin "2") (pinfunction "2_2") (pintype "passive"))
      (node (ref "C512") (pin "2") (pinfunction "2_2") (pintype "passive"))
      (node (ref "C513") (pin "2") (pinfunction "2_2") (pintype "passive"))
      (node (ref "C514") (pin "2") (pinfunction "2_2") (pintype "passive"))
      (node (ref "C515") (pin "2") (pinfunction "2_2") (pintype "passive"))
      (node (ref "C516") (pin "2") (pinfunction "2_2") (pintype "passive"))
      (node (ref "C517") (pin "2") (pinfunction "2_2") (pintype "passive"))
      (node (ref "C518") (pin "2") (pinfunction "2_2") (pintype "passive"))
      (node (ref "C519") (pin "2") (pinfunction "2_2") (pintype "passive"))
      (node (ref "C520") (pin "2") (pinfunction "2_2") (pintype "passive"))
      (node (ref "C521") (pin "2") (pinfunction "2_2") (pintype "passive"))
      (node (ref "C522") (pin "2") (pinfunction "2_2") (pintype "passive"))
      (node (ref "C523") (pin "2") (pinfunction "2_2") (pintype "passive"))
      (node (ref "C524") (pin "2") (pinfunction "2_2") (pintype "passive"))
      (node (ref "C525") (pin "2") (pinfunction "2_2") (pintype "passive"))
      (node (ref "C526") (pin "2") (pinfunction "2_2") (pintype "passive"))
      (node (ref "C527") (pin "2") (pinfunction "2_2") (pintype "passive"))
      (node (ref "C528") (pin "2") (pinfunction "2_2") (pintype "passive"))
      (node (ref "C529") (pin "2") (pinfunction "2_2") (pintype "passive"))
      (node (ref "C530") (pin "2") (pinfunction "2_2") (pintype "passive"))
      (node (ref "C531") (pin "2") (pinfunction "2_2") (pintype "passive"))
      (node (ref "C532") (pin "2") (pinfunction "2_2") (pintype "passive"))
      (node (ref "C533") (pin "2") (pinfunction "2_2") (pintype "passive"))
      (node (ref "C534") (pin "2") (pinfunction "2_2") (pintype "passive"))
      (node (ref "C535") (pin "2") (pinfunction "2_2") (pintype "passive"))
      (node (ref "C536") (pin "2") (pinfunction "2_2") (pintype "passive"))
      (node (ref "C537") (pin "2") (pinfunction "2_2") (pintype "passive"))
      (node (ref "C538") (pin "2") (pinfunction "2_2") (pintype "passive"))
      (node (ref "C539") (pin "2") (pinfunction "2_2") (pintype "passive"))
      (node (ref "C540") (pin "2") (pinfunction "2_2") (pintype "passive"))
      (node (ref "C541") (pin "2") (pinfunction "2_2") (pintype "passive"))
      (node (ref "C542") (pin "2") (pinfunction "2_2") (pintype "passive"))
      (node (ref "C543") (pin "2") (pinfunction "2_2") (pintype "passive"))
      (node (ref "C544") (pin "2") (pinfunction "2_2") (pintype "passive"))
      (node (ref "C545") (pin "2") (pinfunction "2_2") (pintype "passive"))
      (node (ref "C546") (pin "2") (pinfunction "2_2") (pintype "passive"))
      (node (ref "C547") (pin "2") (pinfunction "2_2") (pintype "passive"))
      (node (ref "U27") (pin "11") (pinfunction "VDD_11") (pintype "power_in"))
      (node (ref "U27") (pin "17") (pinfunction "VDD_17") (pintype "power_in"))
      (node (ref "U27") (pin "21") (pinfunction "VDD_21") (pintype "power_in"))
      (node (ref "U27") (pin "25") (pinfunction "VDD_25") (pintype "power_in"))
      (node (ref "U27") (pin "32") (pinfunction "VDD_32") (pintype "power_in"))
      (node (ref "U27") (pin "36") (pinfunction "VDD_36") (pintype "power_in"))
      (node (ref "U27") (pin "4") (pinfunction "VDD_4") (pintype "power_in"))
      (node (ref "U27") (pin "40") (pinfunction "VDD_40") (pintype "power_in"))
      (node (ref "U27") (pin "47") (pinfunction "VDD_47") (pintype "power_in"))
      (node (ref "U27") (pin "51") (pinfunction "VDD_51") (pintype "power_in"))
      (node (ref "U27") (pin "7") (pinfunction "VDD_7") (pintype "power_in"))
      (node (ref "U28") (pin "11") (pinfunction "VDD_11") (pintype "power_in"))
      (node (ref "U28") (pin "17") (pinfunction "VDD_17") (pintype "power_in"))
      (node (ref "U28") (pin "21") (pinfunction "VDD_21") (pintype "power_in"))
      (node (ref "U28") (pin "25") (pinfunction "VDD_25") (pintype "power_in"))
      (node (ref "U28") (pin "32") (pinfunction "VDD_32") (pintype "power_in"))
      (node (ref "U28") (pin "36") (pinfunction "VDD_36") (pintype "power_in"))
      (node (ref "U28") (pin "4") (pinfunction "VDD_4") (pintype "power_in"))
      (node (ref "U28") (pin "40") (pinfunction "VDD_40") (pintype "power_in"))
      (node (ref "U28") (pin "47") (pinfunction "VDD_47") (pintype "power_in"))
      (node (ref "U28") (pin "51") (pinfunction "VDD_51") (pintype "power_in"))
      (node (ref "U28") (pin "7") (pinfunction "VDD_7") (pintype "power_in"))
      (node (ref "U29") (pin "11") (pinfunction "VDD_11") (pintype "power_in"))
      (node (ref "U29") (pin "17") (pinfunction "VDD_17") (pintype "power_in"))
      (node (ref "U29") (pin "21") (pinfunction "VDD_21") (pintype "power_in"))
      (node (ref "U29") (pin "25") (pinfunction "VDD_25") (pintype "power_in"))
      (node (ref "U29") (pin "32") (pinfunction "VDD_32") (pintype "power_in"))
      (node (ref "U29") (pin "36") (pinfunction "VDD_36") (pintype "power_in"))
      (node (ref "U29") (pin "4") (pinfunction "VDD_4") (pintype "power_in"))
      (node (ref "U29") (pin "40") (pinfunction "VDD_40") (pintype "power_in"))
      (node (ref "U29") (pin "47") (pinfunction "VDD_47") (pintype "power_in"))
      (node (ref "U29") (pin "51") (pinfunction "VDD_51") (pintype "power_in"))
      (node (ref "U29") (pin "7") (pinfunction "VDD_7") (pintype "power_in"))
      (node (ref "U30") (pin "11") (pinfunction "VDD_11") (pintype "power_in"))
      (node (ref "U30") (pin "17") (pinfunction "VDD_17") (pintype "power_in"))
      (node (ref "U30") (pin "21") (pinfunction "VDD_21") (pintype "power_in"))
      (node (ref "U30") (pin "25") (pinfunction "VDD_25") (pintype "power_in"))
      (node (ref "U30") (pin "32") (pinfunction "VDD_32") (pintype "power_in"))
      (node (ref "U30") (pin "36") (pinfunction "VDD_36") (pintype "power_in"))
      (node (ref "U30") (pin "4") (pinfunction "VDD_4") (pintype "power_in"))
      (node (ref "U30") (pin "40") (pinfunction "VDD_40") (pintype "power_in"))
      (node (ref "U30") (pin "47") (pinfunction "VDD_47") (pintype "power_in"))
      (node (ref "U30") (pin "51") (pinfunction "VDD_51") (pintype "power_in"))
      (node (ref "U30") (pin "7") (pinfunction "VDD_7") (pintype "power_in"))
      (node (ref "U31") (pin "11") (pinfunction "VDD_11") (pintype "power_in"))
      (node (ref "U31") (pin "17") (pinfunction "VDD_17") (pintype "power_in"))
      (node (ref "U31") (pin "21") (pinfunction "VDD_21") (pintype "power_in"))
      (node (ref "U31") (pin "25") (pinfunction "VDD_25") (pintype "power_in"))
      (node (ref "U31") (pin "32") (pinfunction "VDD_32") (pintype "power_in"))
      (node (ref "U31") (pin "36") (pinfunction "VDD_36") (pintype "power_in"))
      (node (ref "U31") (pin "4") (pinfunction "VDD_4") (pintype "power_in"))
      (node (ref "U31") (pin "40") (pinfunction "VDD_40") (pintype "power_in"))
      (node (ref "U31") (pin "47") (pinfunction "VDD_47") (pintype "power_in"))
      (node (ref "U31") (pin "51") (pinfunction "VDD_51") (pintype "power_in"))
      (node (ref "U31") (pin "7") (pinfunction "VDD_7") (pintype "power_in"))
      (node (ref "U32") (pin "11") (pinfunction "VDD_11") (pintype "power_in"))
      (node (ref "U32") (pin "17") (pinfunction "VDD_17") (pintype "power_in"))
      (node (ref "U32") (pin "21") (pinfunction "VDD_21") (pintype "power_in"))
      (node (ref "U32") (pin "25") (pinfunction "VDD_25") (pintype "power_in"))
      (node (ref "U32") (pin "32") (pinfunction "VDD_32") (pintype "power_in"))
      (node (ref "U32") (pin "36") (pinfunction "VDD_36") (pintype "power_in"))
      (node (ref "U32") (pin "4") (pinfunction "VDD_4") (pintype "power_in"))
      (node (ref "U32") (pin "40") (pinfunction "VDD_40") (pintype "power_in"))
      (node (ref "U32") (pin "47") (pinfunction "VDD_47") (pintype "power_in"))
      (node (ref "U32") (pin "51") (pinfunction "VDD_51") (pintype "power_in"))
      (node (ref "U32") (pin "7") (pinfunction "VDD_7") (pintype "power_in"))
      (node (ref "U33") (pin "11") (pinfunction "VDD_11") (pintype "power_in"))
      (node (ref "U33") (pin "17") (pinfunction "VDD_17") (pintype "power_in"))
      (node (ref "U33") (pin "21") (pinfunction "VDD_21") (pintype "power_in"))
      (node (ref "U33") (pin "25") (pinfunction "VDD_25") (pintype "power_in"))
      (node (ref "U33") (pin "32") (pinfunction "VDD_32") (pintype "power_in"))
      (node (ref "U33") (pin "36") (pinfunction "VDD_36") (pintype "power_in"))
      (node (ref "U33") (pin "4") (pinfunction "VDD_4") (pintype "power_in"))
      (node (ref "U33") (pin "40") (pinfunction "VDD_40") (pintype "power_in"))
      (node (ref "U33") (pin "47") (pinfunction "VDD_47") (pintype "power_in"))
      (node (ref "U33") (pin "51") (pinfunction "VDD_51") (pintype "power_in"))
      (node (ref "U33") (pin "7") (pinfunction "VDD_7") (pintype "power_in"))
      (node (ref "U34") (pin "11") (pinfunction "VDD_11") (pintype "power_in"))
      (node (ref "U34") (pin "17") (pinfunction "VDD_17") (pintype "power_in"))
      (node (ref "U34") (pin "21") (pinfunction "VDD_21") (pintype "power_in"))
      (node (ref "U34") (pin "25") (pinfunction "VDD_25") (pintype "power_in"))
      (node (ref "U34") (pin "32") (pinfunction "VDD_32") (pintype "power_in"))
      (node (ref "U34") (pin "36") (pinfunction "VDD_36") (pintype "power_in"))
      (node (ref "U34") (pin "4") (pinfunction "VDD_4") (pintype "power_in"))
      (node (ref "U34") (pin "40") (pinfunction "VDD_40") (pintype "power_in"))
      (node (ref "U34") (pin "47") (pinfunction "VDD_47") (pintype "power_in"))
      (node (ref "U34") (pin "51") (pinfunction "VDD_51") (pintype "power_in"))
      (node (ref "U34") (pin "7") (pinfunction "VDD_7") (pintype "power_in"))
    )
    (net (code "57") (name "VPLL4") (class "Default")
      (node (ref "C420") (pin "1") (pinfunction "1_1") (pintype "passive"))
      (node (ref "C422") (pin "1") (pinfunction "1_1") (pintype "passive"))
      (node (ref "C424") (pin "1") (pinfunction "1_1") (pintype "passive"))
      (node (ref "C426") (pin "1") (pinfunction "1_1") (pintype "passive"))
      (node (ref "C484") (pin "1") (pinfunction "1_1") (pintype "passive"))
      (node (ref "C486") (pin "1") (pinfunction "1_1") (pintype "passive"))
      (node (ref "C488") (pin "1") (pinfunction "1_1") (pintype "passive"))
      (node (ref "C490") (pin "1") (pinfunction "1_1") (pintype "passive"))
      (node (ref "FB25") (pin "2") (pinfunction "2_2") (pintype "passive"))
      (node (ref "FB26") (pin "2") (pinfunction "2_2") (pintype "passive"))
      (node (ref "FB27") (pin "2") (pinfunction "2_2") (pintype "passive"))
      (node (ref "FB28") (pin "2") (pinfunction "2_2") (pintype "passive"))
      (node (ref "FB29") (pin "2") (pinfunction "2_2") (pintype "passive"))
      (node (ref "FB30") (pin "2") (pinfunction "2_2") (pintype "passive"))
      (node (ref "FB31") (pin "2") (pinfunction "2_2") (pintype "passive"))
      (node (ref "FB32") (pin "2") (pinfunction "2_2") (pintype "passive"))
      (node (ref "U27") (pin "54") (pinfunction "PLL_DVDD_54") (pintype "power_in"))
      (node (ref "U28") (pin "54") (pinfunction "PLL_DVDD_54") (pintype "power_in"))
      (node (ref "U29") (pin "54") (pinfunction "PLL_DVDD_54") (pintype "power_in"))
      (node (ref "U30") (pin "54") (pinfunction "PLL_DVDD_54") (pintype "power_in"))
      (node (ref "U31") (pin "54") (pinfunction "PLL_DVDD_54") (pintype "power_in"))
      (node (ref "U32") (pin "54") (pinfunction "PLL_DVDD_54") (pintype "power_in"))
      (node (ref "U33") (pin "54") (pinfunction "PLL_DVDD_54") (pintype "power_in"))
      (node (ref "U34") (pin "54") (pinfunction "PLL_DVDD_54") (pintype "power_in"))
    )
    (net (code "58") (name "unconnected-(U27-CMODE-Pad44)") (class "Default")
      (node (ref "U27") (pin "44") (pinfunction "CMODE_44") (pintype "passive+no_connect"))
    )
    (net (code "59") (name "unconnected-(U27-RF-Pad49)") (class "Default")
      (node (ref "U27") (pin "49") (pinfunction "RF_49") (pintype "output+no_connect"))
    )
    (net (code "60") (name "unconnected-(U27-TF-Pad48)") (class "Default")
      (node (ref "U27") (pin "48") (pinfunction "TF_48") (pintype "output+no_connect"))
    )
    (net (code "61") (name "unconnected-(U27-XOUT-Pad2)") (class "Default")
      (node (ref "U27") (pin "2") (pinfunction "XOUT_2") (pintype "output"))
    )
    (net (code "62") (name "unconnected-(U28-CMODE-Pad44)") (class "Default")
      (node (ref "U28") (pin "44") (pinfunction "CMODE_44") (pintype "passive+no_connect"))
    )
    (net (code "63") (name "unconnected-(U28-RF-Pad49)") (class "Default")
      (node (ref "U28") (pin "49") (pinfunction "RF_49") (pintype "output+no_connect"))
    )
    (net (code "64") (name "unconnected-(U28-TF-Pad48)") (class "Default")
      (node (ref "U28") (pin "48") (pinfunction "TF_48") (pintype "output+no_connect"))
    )
    (net (code "65") (name "unconnected-(U28-XOUT-Pad2)") (class "Default")
      (node (ref "U28") (pin "2") (pinfunction "XOUT_2") (pintype "output+no_connect"))
    )
    (net (code "66") (name "unconnected-(U29-CMODE-Pad44)") (class "Default")
      (node (ref "U29") (pin "44") (pinfunction "CMODE_44") (pintype "passive+no_connect"))
    )
    (net (code "67") (name "unconnected-(U29-RF-Pad49)") (class "Default")
      (node (ref "U29") (pin "49") (pinfunction "RF_49") (pintype "output+no_connect"))
    )
    (net (code "68") (name "unconnected-(U29-TF-Pad48)") (class "Default")
      (node (ref "U29") (pin "48") (pinfunction "TF_48") (pintype "output+no_connect"))
    )
    (net (code "69") (name "unconnected-(U29-XOUT-Pad2)") (class "Default")
      (node (ref "U29") (pin "2") (pinfunction "XOUT_2") (pintype "output+no_connect"))
    )
    (net (code "70") (name "unconnected-(U30-CMODE-Pad44)") (class "Default")
      (node (ref "U30") (pin "44") (pinfunction "CMODE_44") (pintype "passive+no_connect"))
    )
    (net (code "71") (name "unconnected-(U30-RF-Pad49)") (class "Default")
      (node (ref "U30") (pin "49") (pinfunction "RF_49") (pintype "output+no_connect"))
    )
    (net (code "72") (name "unconnected-(U30-TF-Pad48)") (class "Default")
      (node (ref "U30") (pin "48") (pinfunction "TF_48") (pintype "output+no_connect"))
    )
    (net (code "73") (name "unconnected-(U30-XOUT-Pad2)") (class "Default")
      (node (ref "U30") (pin "2") (pinfunction "XOUT_2") (pintype "output+no_connect"))
    )
    (net (code "74") (name "unconnected-(U31-CMODE-Pad44)") (class "Default")
      (node (ref "U31") (pin "44") (pinfunction "CMODE_44") (pintype "passive+no_connect"))
    )
    (net (code "75") (name "unconnected-(U31-RF-Pad49)") (class "Default")
      (node (ref "U31") (pin "49") (pinfunction "RF_49") (pintype "output+no_connect"))
    )
    (net (code "76") (name "unconnected-(U31-TF-Pad48)") (class "Default")
      (node (ref "U31") (pin "48") (pinfunction "TF_48") (pintype "output+no_connect"))
    )
    (net (code "77") (name "unconnected-(U31-XOUT-Pad2)") (class "Default")
      (node (ref "U31") (pin "2") (pinfunction "XOUT_2") (pintype "output+no_connect"))
    )
    (net (code "78") (name "unconnected-(U32-CMODE-Pad44)") (class "Default")
      (node (ref "U32") (pin "44") (pinfunction "CMODE_44") (pintype "passive+no_connect"))
    )
    (net (code "79") (name "unconnected-(U32-RF-Pad49)") (class "Default")
      (node (ref "U32") (pin "49") (pinfunction "RF_49") (pintype "output+no_connect"))
    )
    (net (code "80") (name "unconnected-(U32-TF-Pad48)") (class "Default")
      (node (ref "U32") (pin "48") (pinfunction "TF_48") (pintype "output+no_connect"))
    )
    (net (code "81") (name "unconnected-(U32-XOUT-Pad2)") (class "Default")
      (node (ref "U32") (pin "2") (pinfunction "XOUT_2") (pintype "output+no_connect"))
    )
    (net (code "82") (name "unconnected-(U33-CMODE-Pad44)") (class "Default")
      (node (ref "U33") (pin "44") (pinfunction "CMODE_44") (pintype "passive+no_connect"))
    )
    (net (code "83") (name "unconnected-(U33-RF-Pad49)") (class "Default")
      (node (ref "U33") (pin "49") (pinfunction "RF_49") (pintype "output+no_connect"))
    )
    (net (code "84") (name "unconnected-(U33-TF-Pad48)") (class "Default")
      (node (ref "U33") (pin "48") (pinfunction "TF_48") (pintype "output+no_connect"))
    )
    (net (code "85") (name "unconnected-(U33-XOUT-Pad2)") (class "Default")
      (node (ref "U33") (pin "2") (pinfunction "XOUT_2") (pintype "output+no_connect"))
    )
    (net (code "86") (name "unconnected-(U34-BO-Pad34)") (class "Default")
      (node (ref "U34") (pin "34") (pinfunction "BO_34") (pintype "output+no_connect"))
    )
    (net (code "87") (name "unconnected-(U34-CLKOUT-Pad39)") (class "Default")
      (node (ref "U34") (pin "39") (pinfunction "CLKOUT_39") (pintype "output+no_connect"))
    )
    (net (code "88") (name "unconnected-(U34-CMODE-Pad44)") (class "Default")
      (node (ref "U34") (pin "44") (pinfunction "CMODE_44") (pintype "passive+no_connect"))
    )
    (net (code "89") (name "unconnected-(U34-CO-Pad38)") (class "Default")
      (node (ref "U34") (pin "38") (pinfunction "CO_38") (pintype "output+no_connect"))
    )
    (net (code "90") (name "unconnected-(U34-NRSTO-Pad33)") (class "Default")
      (node (ref "U34") (pin "33") (pinfunction "NRSTO_33") (pintype "output+no_connect"))
    )
    (net (code "91") (name "unconnected-(U34-XOUT-Pad2)") (class "Default")
      (node (ref "U34") (pin "2") (pinfunction "XOUT_2") (pintype "output+no_connect"))
    )
  )
)
